# Sheet1.net
KiCad netlist of a schematic drawn in Altium Designer
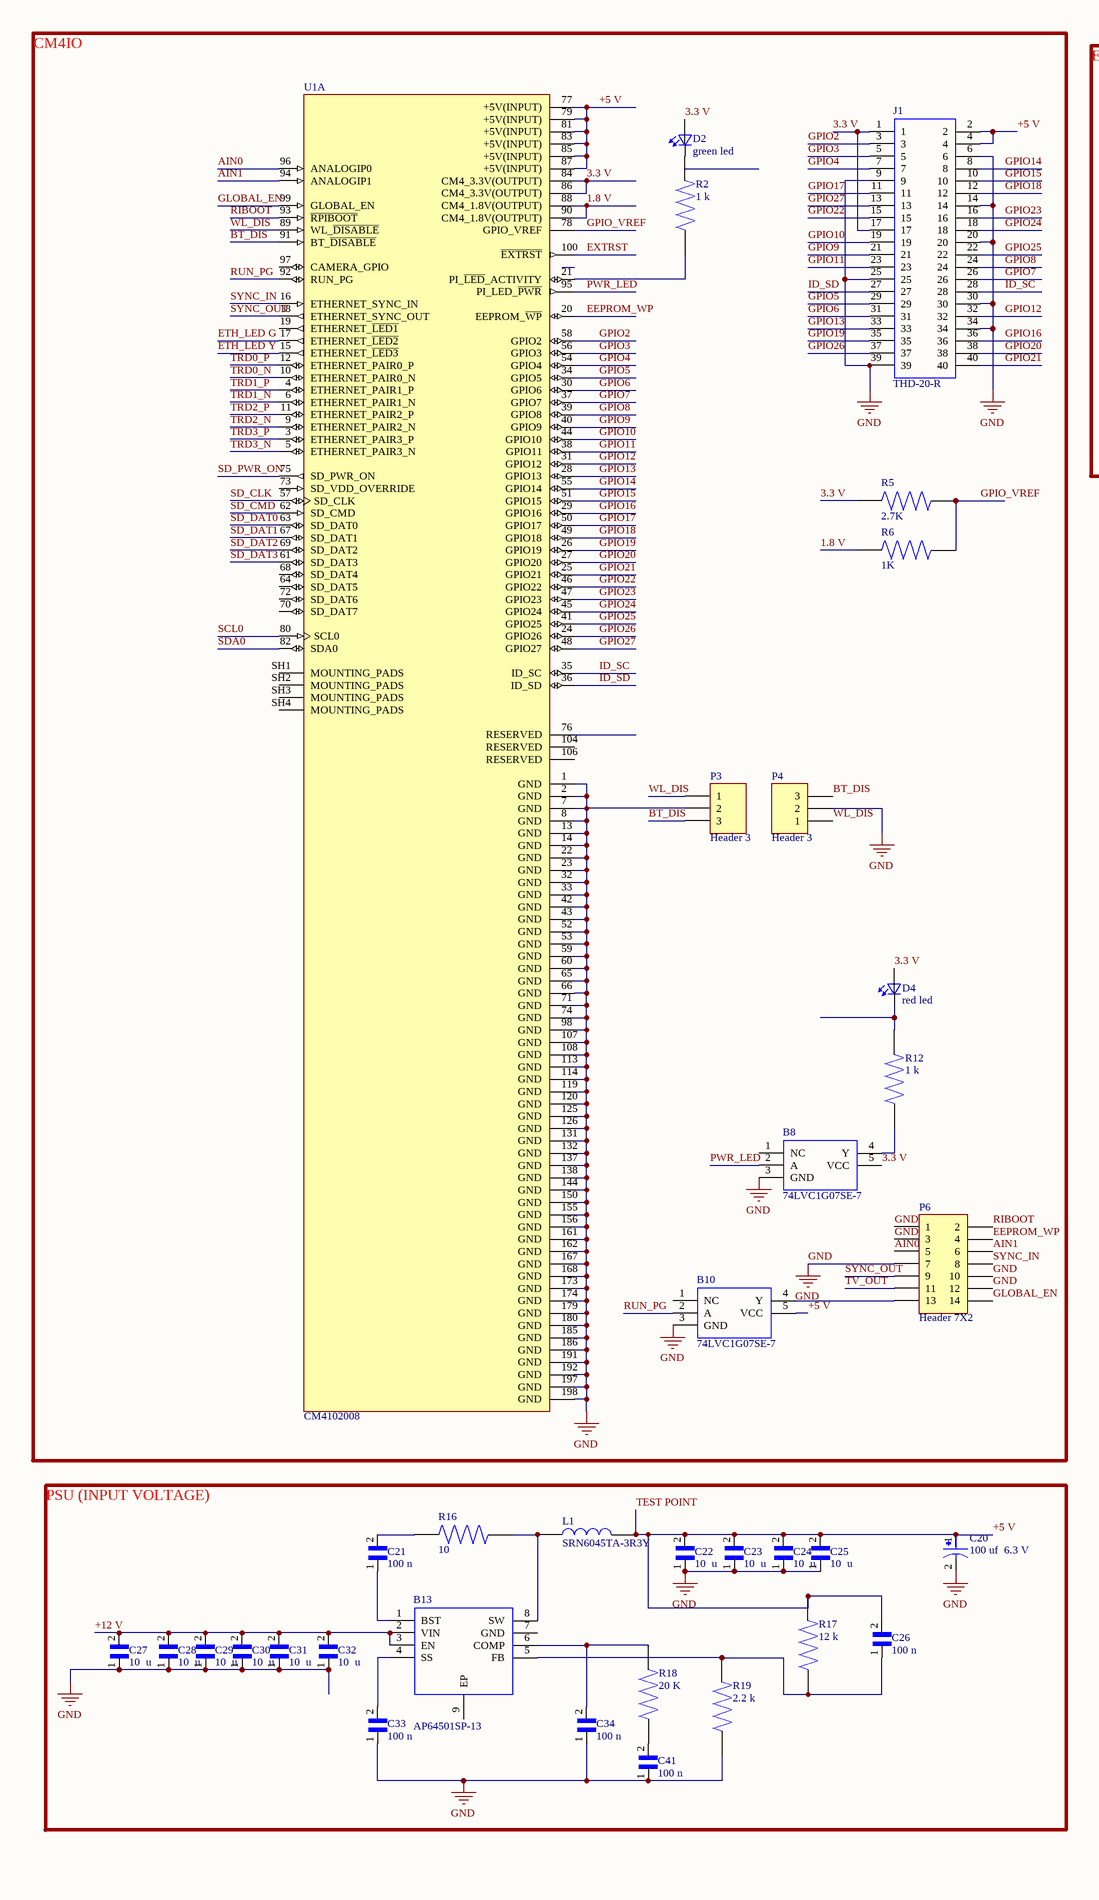
[diagram p0: Sheet1.SchDoc, left]
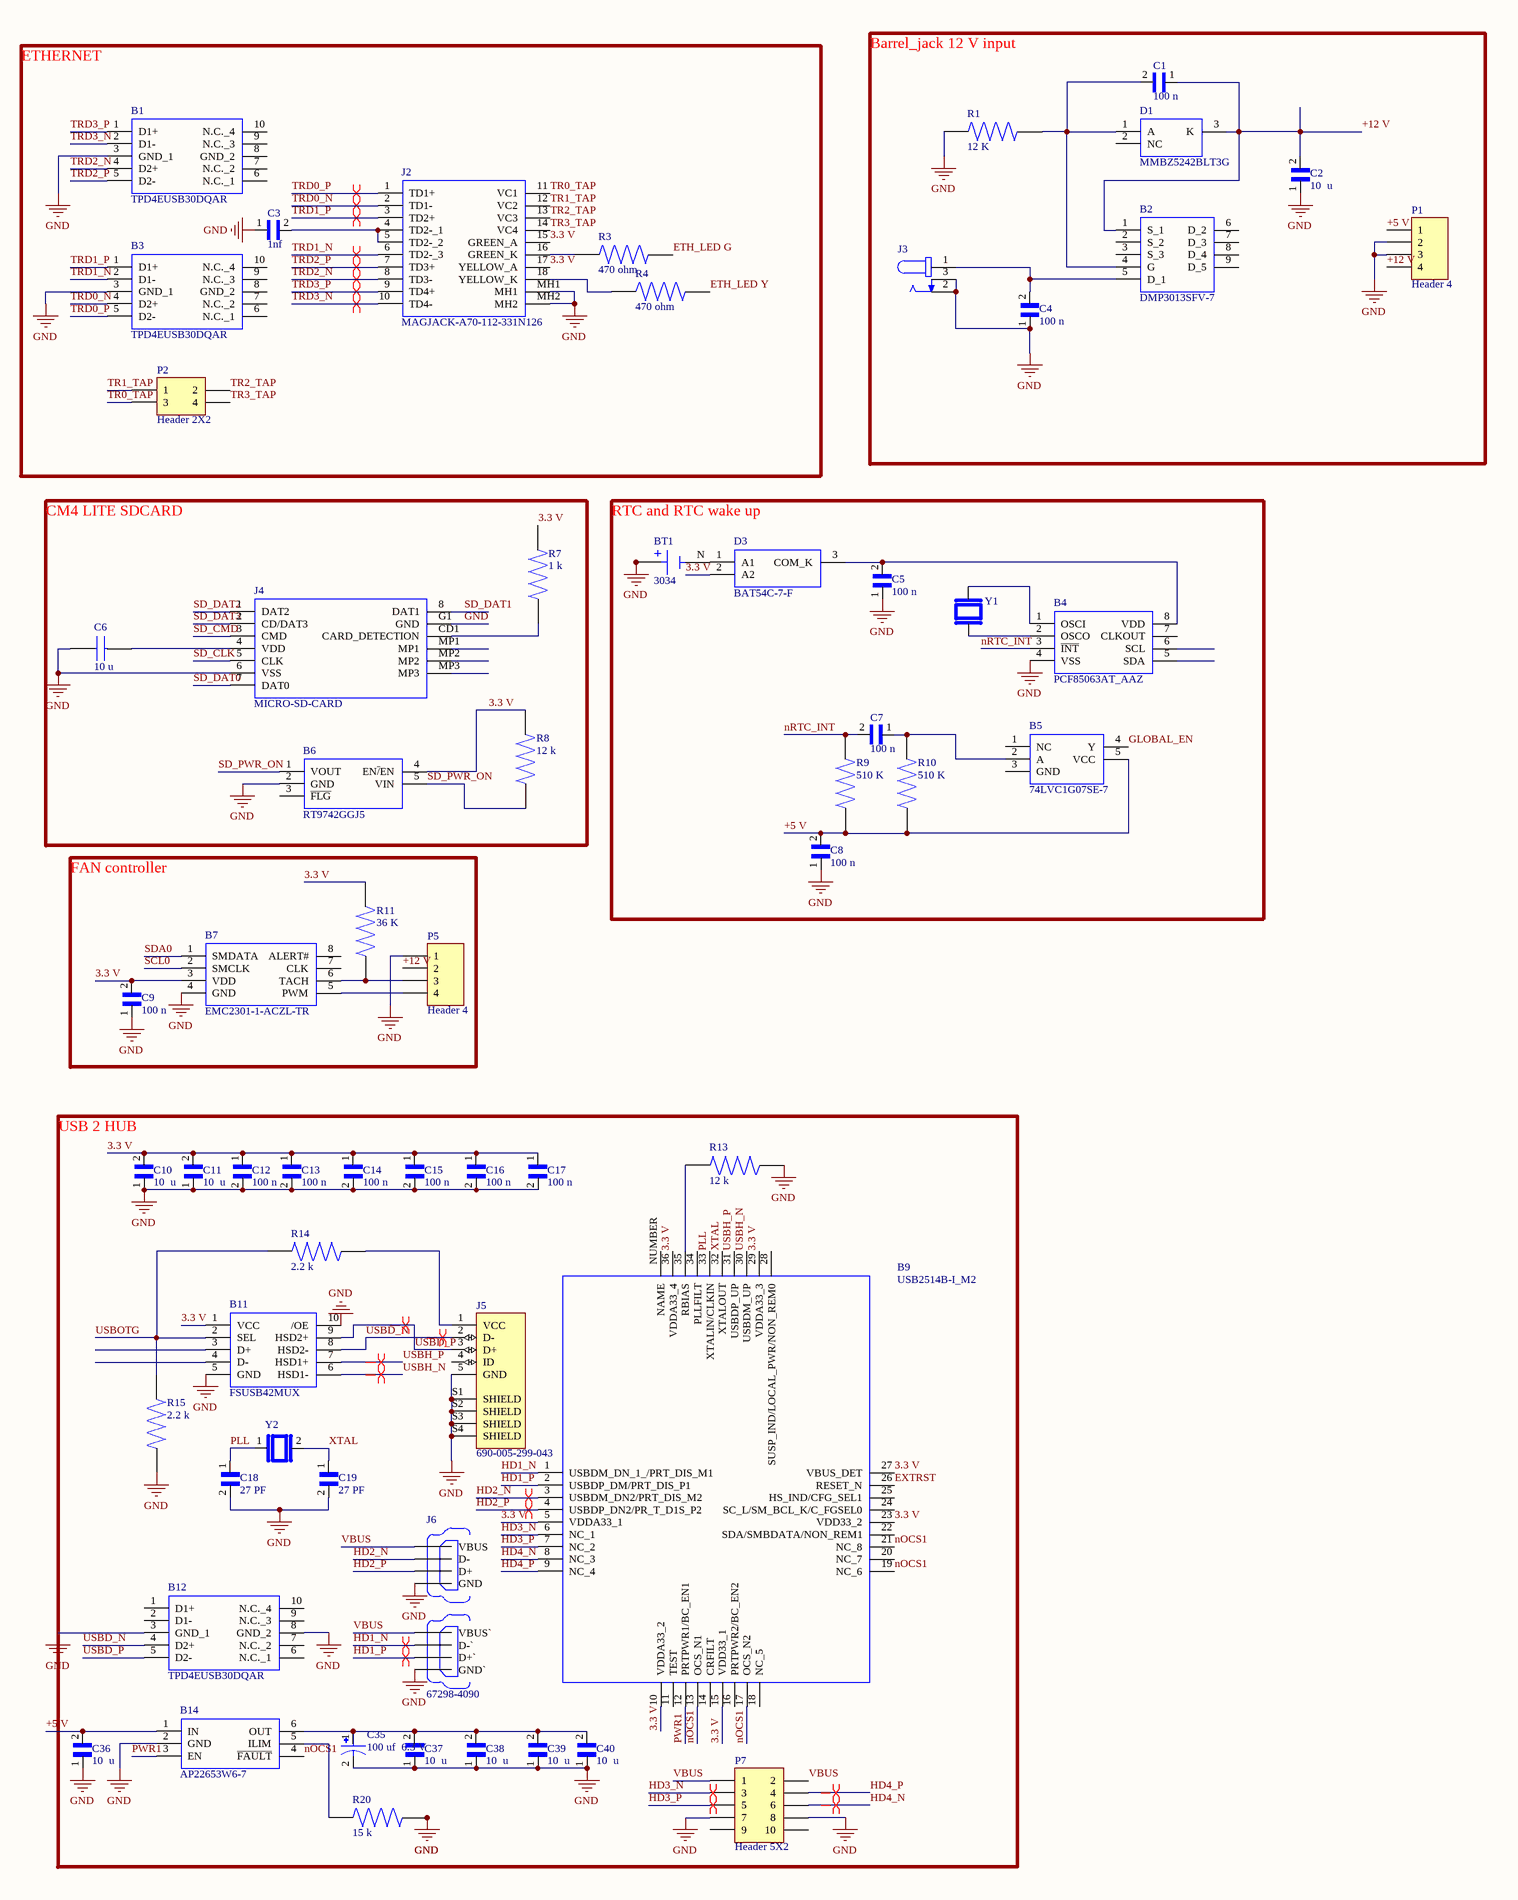
[diagram p1: Sheet1.SchDoc, right]

(export (version "E")
  (design (tool "Eeschema 10.0.6"))
  (components
    (comp (ref "B1")
      (value "TPD4EUSB30DQAR")
      (footprint "DQA_R-PUSON-N10_:DQA(R-PUSON-N10)")
      (description "Texas Instruments TPD4EUSB30DQAR, USB Controller, 6Gbit/s, USB 3.0, 10-Pin SON")
      (fields (field (name "MOUSER PART NUMBER") "595-TPD4EUSB30DQAR"))
      (libsource (lib "Miscellaneous Devices") (part "TPD4EUSB30DQAR"))
    )
    (comp (ref "B2")
      (value "DMP3013SFV-7")
      (footprint "DMP3036SFV7:DMP3036SFV7")
      (description "Trans MOSFET P-CH 30V 12A 8-Pin PowerDI EP T/R")
      (fields (field (name "MOUSER PART NUMBER") "621-DMP3013SFV-7"))
      (libsource (lib "Miscellaneous Devices") (part "DMP3013SFV-7"))
    )
    (comp (ref "B3")
      (value "TPD4EUSB30DQAR")
      (footprint "DQA_R-PUSON-N10_:DQA(R-PUSON-N10)")
      (description "Texas Instruments TPD4EUSB30DQAR, USB Controller, 6Gbit/s, USB 3.0, 10-Pin SON")
      (fields (field (name "MOUSER PART NUMBER") "595-TPD4EUSB30DQAR"))
      (libsource (lib "Miscellaneous Devices") (part "TPD4EUSB30DQAR"))
    )
    (comp (ref "B4")
      (value "PCF85063AT_AAZ")
      (footprint "SOIC127P600X175-8N")
      (description "Real Time Clock Low Power Real time clocks")
      (fields
        (field (name "MANUFACTURER_PART_NUMBER") "PCF85063AT/AAZ")
        (field (name "MOUSER PART NUMBER") "771-PCF85063AT/AAZ")
      )
      (libsource (lib "Miscellaneous Devices") (part "PCF85063AT_AAZ"))
    )
    (comp (ref "B5")
      (value "74LVC1G07SE-7")
      (footprint "SOT65P210X110-5N")
      (description "Buffers & Line Drivers Single Gate Open Out 1.65 to 5.5V 32mA")
      (fields (field (name "MOUSER PART NUMBER") "621-74LVC1G07SE-7"))
      (libsource (lib "Miscellaneous Devices") (part "74LVC1G07SE-7"))
    )
    (comp (ref "B6")
      (value "RT9742GGJ5")
      (footprint "SOT94P280X100-5N")
      (fields (field (name "MOUSER PART NUMBER") "835-RT9742GGJ5"))
      (libsource (lib "Miscellaneous Devices") (part "RT9742GGJ5"))
    )
    (comp (ref "B7")
      (value "EMC2301-1-ACZL-TR")
      (footprint "SOP65P490X110-8N")
      (description "RPM-Based PWM Fan Speed Controller MSOP8")
      (fields (field (name "MOUSER PART NUMBER") "886-EMC2301-1-ACZLTR"))
      (libsource (lib "Miscellaneous Devices") (part "EMC2301-1-ACZL-TR"))
    )
    (comp (ref "B8")
      (value "74LVC1G07SE-7")
      (footprint "SOT65P210X110-5N")
      (description "Buffers & Line Drivers Single Gate Open Out 1.65 to 5.5V 32mA")
      (fields (field (name "MOUSER PART NUMBER") "621-74LVC1G07SE-7"))
      (libsource (lib "Miscellaneous Devices") (part "74LVC1G07SE-7"))
    )
    (comp (ref "B9")
      (value "USB2514B-I_M2")
      (footprint "QFN50P600X600X100-37N-D")
      (description "Microchip USB2514B-I/M2, USB Controller, USB 2.0, 3.3 V, 36-Pin SQFN")
      (fields
        (field (name "MANUFACTURER_PART_NUMBER") "USB2514B-I/M2")
        (field (name "MOUSER PART NUMBER") "579-USB2514B-I/M2")
      )
      (libsource (lib "Miscellaneous Devices") (part "USB2514B-I_M2"))
    )
    (comp (ref "B10")
      (value "74LVC1G07SE-7")
      (footprint "SOT65P210X110-5N")
      (description "Buffers & Line Drivers Single Gate Open Out 1.65 to 5.5V 32mA")
      (fields (field (name "MOUSER PART NUMBER") "621-74LVC1G07SE-7"))
      (libsource (lib "Miscellaneous Devices") (part "74LVC1G07SE-7"))
    )
    (comp (ref "B11")
      (value "FSUSB42MUX")
      (footprint "SOP50P490X110-10N")
      (fields (field (name "MOUSER PART NUMBER") "512-FSUSB42MUX"))
      (libsource (lib "Miscellaneous Devices") (part "FSUSB42MUX"))
    )
    (comp (ref "B12")
      (value "TPD4EUSB30DQAR")
      (footprint "DQA_R-PUSON-N10_:DQA(R-PUSON-N10)")
      (description "Texas Instruments TPD4EUSB30DQAR, USB Controller, 6Gbit/s, USB 3.0, 10-Pin SON")
      (fields (field (name "MOUSER PART NUMBER") "595-TPD4EUSB30DQAR"))
      (libsource (lib "Miscellaneous Devices") (part "TPD4EUSB30DQAR"))
    )
    (comp (ref "B13")
      (value "AP64501SP-13")
      (footprint "SOIC127P600X163-9N")
      (description "Conv DC-DC 3.8V to 40V Synchronous Step Down Single-Out 0.8V to 39V 5A 8-Pin SO EP T/R")
      (fields (field (name "MOUSER PART NUMBER") "621-AP64501SP-13"))
      (libsource (lib "Miscellaneous Devices") (part "AP64501SP-13"))
    )
    (comp (ref "B14")
      (value "AP22653W6-7")
      (footprint "SOT95P280X145-6N")
      (description "Power Switch ICs - Power Distribution 1-Ch Precision Curr-Limit Load SW")
      (fields (field (name "MOUSER PART NUMBER") "621-AP22653W6-7"))
      (libsource (lib "Miscellaneous Devices") (part "AP22653W6-7"))
    )
    (comp (ref "BT1")
      (value "3034")
      (footprint "BAT_3034:BAT_3034")
      (description "SMT Holder for 20mm Cell-Tin Nickel Plate")
      (fields (field (name "MF") "Keystone Electronics Corp."))
      (libsource (lib "Miscellaneous Devices") (part "3034"))
    )
    (comp (ref "C1")
      (value "100 n")
      (footprint "CAPC1005X55N:CAPC1005X55N")
      (description "C Series 0402 0.1 uF 16 V Â±20 % Tolerance X7R SMT Multilayer Ceramic Capacitor")
      (fields (field (name "MP") "C1005X7R1C104M050BC") (field (name "MF") "TDK"))
      (libsource (lib "") (part "C1005X7R1C104M050BC_3"))
    )
    (comp (ref "C2")
      (value "10  u")
      (footprint "CAPC1005X55N:CAPC1005X55N")
      (description "C Series 0805 10 uF 16 V Â±10 % Tolerance X6S SMT Multilayer Ceramic Capacitor")
      (fields (field (name "MP") "C2012X6S1C106K125AC") (field (name "MF") "TDK"))
      (libsource (lib "Miscellaneous Devices") (part "C2012X6S1C106K125AC"))
    )
    (comp (ref "C3")
      (value "1nf")
      (footprint "CAPC1005X55N:CAPC1005X55N")
      (description "C Series 0402 0.1 uF 16 V Â±20 % Tolerance X7R SMT Multilayer Ceramic Capacitor")
      (fields (field (name "MP") "C1005X7R1C104M050BC") (field (name "MF") "TDK"))
      (libsource (lib "") (part "C1005X7R1C104M050BC_2"))
    )
    (comp (ref "C4")
      (value "100 n")
      (footprint "CAPC1005X55N:CAPC1005X55N")
      (description "C Series 0402 0.1 uF 16 V Â±20 % Tolerance X7R SMT Multilayer Ceramic Capacitor")
      (fields (field (name "MP") "C1005X7R1C104M050BC") (field (name "MF") "TDK"))
      (libsource (lib "") (part "C1005X7R1C104M050BC_1"))
    )
    (comp (ref "C5")
      (value "100 n")
      (footprint "CAPC1005X55N:CAPC1005X55N")
      (description "C Series 0402 0.1 uF 16 V Â±20 % Tolerance X7R SMT Multilayer Ceramic Capacitor")
      (fields (field (name "MP") "C1005X7R1C104M050BC") (field (name "MF") "TDK"))
      (libsource (lib "") (part "C1005X7R1C104M050BC_1"))
    )
    (comp (ref "C6")
      (value "10 u")
      (footprint "CAPC2012X145N:CAPC2012X145N")
      (description "Multilayer Ceramic Capacitors MLCC - SMD/SMT 0805 10uF 35volts *Derate Voltage/Temp")
      (fields
        (field (name "MOUSER PART NUMBER") "81-GRM21BC8YA106ME1L")
        (field (name "MANUFACTURER_PART_NUMBER") "GRM21BC8YA106ME11L")
      )
      (libsource (lib "Miscellaneous Devices") (part "GRM21BC8YA106ME11L"))
    )
    (comp (ref "C7")
      (value "100 n")
      (footprint "CAPC1005X55N:CAPC1005X55N")
      (description "C Series 0402 0.1 uF 16 V Â±20 % Tolerance X7R SMT Multilayer Ceramic Capacitor")
      (fields (field (name "MP") "C1005X7R1C104M050BC") (field (name "MF") "TDK"))
      (libsource (lib "") (part "C1005X7R1C104M050BC_3"))
    )
    (comp (ref "C8")
      (value "100 n")
      (footprint "CAPC1005X55N:CAPC1005X55N")
      (description "C Series 0402 0.1 uF 16 V Â±20 % Tolerance X7R SMT Multilayer Ceramic Capacitor")
      (fields (field (name "MP") "C1005X7R1C104M050BC") (field (name "MF") "TDK"))
      (libsource (lib "") (part "C1005X7R1C104M050BC_1"))
    )
    (comp (ref "C9")
      (value "100 n")
      (footprint "CAPC1005X55N:CAPC1005X55N")
      (description "C Series 0402 0.1 uF 16 V Â±20 % Tolerance X7R SMT Multilayer Ceramic Capacitor")
      (fields (field (name "MP") "C1005X7R1C104M050BC") (field (name "MF") "TDK"))
      (libsource (lib "") (part "C1005X7R1C104M050BC_1"))
    )
    (comp (ref "C10")
      (value "10  u")
      (footprint "CAPC1005X55N:CAPC1005X55N")
      (description "C Series 0805 10 uF 16 V Â±10 % Tolerance X6S SMT Multilayer Ceramic Capacitor")
      (fields (field (name "MP") "C2012X6S1C106K125AC") (field (name "MF") "TDK"))
      (libsource (lib "Miscellaneous Devices") (part "C2012X6S1C106K125AC"))
    )
    (comp (ref "C11")
      (value "10  u")
      (footprint "CAPC1005X55N:CAPC1005X55N")
      (description "C Series 0805 10 uF 16 V Â±10 % Tolerance X6S SMT Multilayer Ceramic Capacitor")
      (fields (field (name "MP") "C2012X6S1C106K125AC") (field (name "MF") "TDK"))
      (libsource (lib "Miscellaneous Devices") (part "C2012X6S1C106K125AC"))
    )
    (comp (ref "C12")
      (value "100 n")
      (footprint "CAPC1005X55N:CAPC1005X55N")
      (description "C Series 0402 0.1 uF 16 V Â±20 % Tolerance X7R SMT Multilayer Ceramic Capacitor")
      (fields (field (name "MP") "C1005X7R1C104M050BC") (field (name "MF") "TDK"))
      (libsource (lib "Miscellaneous Devices") (part "C1005X7R1C104M050BC"))
    )
    (comp (ref "C13")
      (value "100 n")
      (footprint "CAPC1005X55N:CAPC1005X55N")
      (description "C Series 0402 0.1 uF 16 V Â±20 % Tolerance X7R SMT Multilayer Ceramic Capacitor")
      (fields (field (name "MP") "C1005X7R1C104M050BC") (field (name "MF") "TDK"))
      (libsource (lib "Miscellaneous Devices") (part "C1005X7R1C104M050BC"))
    )
    (comp (ref "C14")
      (value "100 n")
      (footprint "CAPC1005X55N:CAPC1005X55N")
      (description "C Series 0402 0.1 uF 16 V Â±20 % Tolerance X7R SMT Multilayer Ceramic Capacitor")
      (fields (field (name "MP") "C1005X7R1C104M050BC") (field (name "MF") "TDK"))
      (libsource (lib "Miscellaneous Devices") (part "C1005X7R1C104M050BC"))
    )
    (comp (ref "C15")
      (value "100 n")
      (footprint "CAPC1005X55N:CAPC1005X55N")
      (description "C Series 0402 0.1 uF 16 V Â±20 % Tolerance X7R SMT Multilayer Ceramic Capacitor")
      (fields (field (name "MP") "C1005X7R1C104M050BC") (field (name "MF") "TDK"))
      (libsource (lib "Miscellaneous Devices") (part "C1005X7R1C104M050BC"))
    )
    (comp (ref "C16")
      (value "100 n")
      (footprint "CAPC1005X55N:CAPC1005X55N")
      (description "C Series 0402 0.1 uF 16 V Â±20 % Tolerance X7R SMT Multilayer Ceramic Capacitor")
      (fields (field (name "MP") "C1005X7R1C104M050BC") (field (name "MF") "TDK"))
      (libsource (lib "Miscellaneous Devices") (part "C1005X7R1C104M050BC"))
    )
    (comp (ref "C17")
      (value "100 n")
      (footprint "CAPC1005X55N:CAPC1005X55N")
      (description "C Series 0402 0.1 uF 16 V Â±20 % Tolerance X7R SMT Multilayer Ceramic Capacitor")
      (fields (field (name "MP") "C1005X7R1C104M050BC") (field (name "MF") "TDK"))
      (libsource (lib "Miscellaneous Devices") (part "C1005X7R1C104M050BC"))
    )
    (comp (ref "C18")
      (value "27 PF")
      (footprint "CAPC1005X55N:CAPC1005X55N")
      (description "C Series 0402 0.1 uF 16 V Â±20 % Tolerance X7R SMT Multilayer Ceramic Capacitor")
      (fields (field (name "MP") "C1005X7R1C104M050BC") (field (name "MF") "TDK"))
      (libsource (lib "Miscellaneous Devices") (part "C1005X7R1C104M050BC"))
    )
    (comp (ref "C19")
      (value "27 PF")
      (footprint "CAPC1005X55N:CAPC1005X55N")
      (description "C Series 0402 0.1 uF 16 V Â±20 % Tolerance X7R SMT Multilayer Ceramic Capacitor")
      (fields (field (name "MP") "C1005X7R1C104M050BC") (field (name "MF") "TDK"))
      (libsource (lib "Miscellaneous Devices") (part "C1005X7R1C104M050BC"))
    )
    (comp (ref "C20")
      (value "100 uf  6.3 V")
      (footprint "CAPMP3528X210N:CAPMP3528X210N")
      (description "100 ÂµF Molded Tantalum Polymer Capacitor 6.3 V 1411 (3528 Metric) 25mOhm @ 100kHz")
      (fields (field (name "MF") "KEMET") (field (name "MP") "T543B107K006AHW025"))
      (libsource (lib "Miscellaneous Devices") (part "T543B107K006AHW025"))
    )
    (comp (ref "C21")
      (value "100 n")
      (footprint "CAPC1005X55N:CAPC1005X55N")
      (description "C Series 0402 0.1 uF 16 V Â±20 % Tolerance X7R SMT Multilayer Ceramic Capacitor")
      (fields (field (name "MP") "C1005X7R1C104M050BC") (field (name "MF") "TDK"))
      (libsource (lib "") (part "C1005X7R1C104M050BC_1"))
    )
    (comp (ref "C22")
      (value "10  u")
      (footprint "CAPC1005X55N:CAPC1005X55N")
      (description "C Series 0805 10 uF 16 V Â±10 % Tolerance X6S SMT Multilayer Ceramic Capacitor")
      (fields (field (name "MP") "C2012X6S1C106K125AC") (field (name "MF") "TDK"))
      (libsource (lib "Miscellaneous Devices") (part "C2012X6S1C106K125AC"))
    )
    (comp (ref "C23")
      (value "10  u")
      (footprint "CAPC1005X55N:CAPC1005X55N")
      (description "C Series 0805 10 uF 16 V Â±10 % Tolerance X6S SMT Multilayer Ceramic Capacitor")
      (fields (field (name "MP") "C2012X6S1C106K125AC") (field (name "MF") "TDK"))
      (libsource (lib "Miscellaneous Devices") (part "C2012X6S1C106K125AC"))
    )
    (comp (ref "C24")
      (value "10  u")
      (footprint "CAPC1005X55N:CAPC1005X55N")
      (description "C Series 0805 10 uF 16 V Â±10 % Tolerance X6S SMT Multilayer Ceramic Capacitor")
      (fields (field (name "MP") "C2012X6S1C106K125AC") (field (name "MF") "TDK"))
      (libsource (lib "Miscellaneous Devices") (part "C2012X6S1C106K125AC"))
    )
    (comp (ref "C25")
      (value "10  u")
      (footprint "CAPC1005X55N:CAPC1005X55N")
      (description "C Series 0805 10 uF 16 V Â±10 % Tolerance X6S SMT Multilayer Ceramic Capacitor")
      (fields (field (name "MP") "C2012X6S1C106K125AC") (field (name "MF") "TDK"))
      (libsource (lib "Miscellaneous Devices") (part "C2012X6S1C106K125AC"))
    )
    (comp (ref "C26")
      (value "100 n")
      (footprint "CAPC1005X55N:CAPC1005X55N")
      (description "C Series 0402 0.1 uF 16 V Â±20 % Tolerance X7R SMT Multilayer Ceramic Capacitor")
      (fields (field (name "MP") "C1005X7R1C104M050BC") (field (name "MF") "TDK"))
      (libsource (lib "") (part "C1005X7R1C104M050BC_1"))
    )
    (comp (ref "C27")
      (value "10  u")
      (footprint "CAPC1005X55N:CAPC1005X55N")
      (description "C Series 0805 10 uF 16 V Â±10 % Tolerance X6S SMT Multilayer Ceramic Capacitor")
      (fields (field (name "MP") "C2012X6S1C106K125AC") (field (name "MF") "TDK"))
      (libsource (lib "Miscellaneous Devices") (part "C2012X6S1C106K125AC"))
    )
    (comp (ref "C28")
      (value "10  u")
      (footprint "CAPC1005X55N:CAPC1005X55N")
      (description "C Series 0805 10 uF 16 V Â±10 % Tolerance X6S SMT Multilayer Ceramic Capacitor")
      (fields (field (name "MP") "C2012X6S1C106K125AC") (field (name "MF") "TDK"))
      (libsource (lib "Miscellaneous Devices") (part "C2012X6S1C106K125AC"))
    )
    (comp (ref "C29")
      (value "10  u")
      (footprint "CAPC1005X55N:CAPC1005X55N")
      (description "C Series 0805 10 uF 16 V Â±10 % Tolerance X6S SMT Multilayer Ceramic Capacitor")
      (fields (field (name "MP") "C2012X6S1C106K125AC") (field (name "MF") "TDK"))
      (libsource (lib "Miscellaneous Devices") (part "C2012X6S1C106K125AC"))
    )
    (comp (ref "C30")
      (value "10  u")
      (footprint "CAPC1005X55N:CAPC1005X55N")
      (description "C Series 0805 10 uF 16 V Â±10 % Tolerance X6S SMT Multilayer Ceramic Capacitor")
      (fields (field (name "MP") "C2012X6S1C106K125AC") (field (name "MF") "TDK"))
      (libsource (lib "Miscellaneous Devices") (part "C2012X6S1C106K125AC"))
    )
    (comp (ref "C31")
      (value "10  u")
      (footprint "CAPC1005X55N:CAPC1005X55N")
      (description "C Series 0805 10 uF 16 V Â±10 % Tolerance X6S SMT Multilayer Ceramic Capacitor")
      (fields (field (name "MP") "C2012X6S1C106K125AC") (field (name "MF") "TDK"))
      (libsource (lib "Miscellaneous Devices") (part "C2012X6S1C106K125AC"))
    )
    (comp (ref "C32")
      (value "10  u")
      (footprint "CAPC1005X55N:CAPC1005X55N")
      (description "C Series 0805 10 uF 16 V Â±10 % Tolerance X6S SMT Multilayer Ceramic Capacitor")
      (fields (field (name "MP") "C2012X6S1C106K125AC") (field (name "MF") "TDK"))
      (libsource (lib "Miscellaneous Devices") (part "C2012X6S1C106K125AC"))
    )
    (comp (ref "C33")
      (value "100 n")
      (footprint "CAPC1005X55N:CAPC1005X55N")
      (description "C Series 0402 0.1 uF 16 V Â±20 % Tolerance X7R SMT Multilayer Ceramic Capacitor")
      (fields (field (name "MP") "C1005X7R1C104M050BC") (field (name "MF") "TDK"))
      (libsource (lib "") (part "C1005X7R1C104M050BC_1"))
    )
    (comp (ref "C34")
      (value "100 n")
      (footprint "CAPC1005X55N:CAPC1005X55N")
      (description "C Series 0402 0.1 uF 16 V Â±20 % Tolerance X7R SMT Multilayer Ceramic Capacitor")
      (fields (field (name "MP") "C1005X7R1C104M050BC") (field (name "MF") "TDK"))
      (libsource (lib "") (part "C1005X7R1C104M050BC_1"))
    )
    (comp (ref "C35")
      (value "100 uf  6.3 V")
      (footprint "CAPMP3528X210N:CAPMP3528X210N")
      (description "100 ÂµF Molded Tantalum Polymer Capacitor 6.3 V 1411 (3528 Metric) 25mOhm @ 100kHz")
      (fields (field (name "MF") "KEMET") (field (name "MP") "T543B107K006AHW025"))
      (libsource (lib "Miscellaneous Devices") (part "T543B107K006AHW025"))
    )
    (comp (ref "C36")
      (value "10  u")
      (footprint "CAPC1005X55N:CAPC1005X55N")
      (description "C Series 0805 10 uF 16 V Â±10 % Tolerance X6S SMT Multilayer Ceramic Capacitor")
      (fields (field (name "MP") "C2012X6S1C106K125AC") (field (name "MF") "TDK"))
      (libsource (lib "Miscellaneous Devices") (part "C2012X6S1C106K125AC"))
    )
    (comp (ref "C37")
      (value "10  u")
      (footprint "CAPC1005X55N:CAPC1005X55N")
      (description "C Series 0805 10 uF 16 V Â±10 % Tolerance X6S SMT Multilayer Ceramic Capacitor")
      (fields (field (name "MP") "C2012X6S1C106K125AC") (field (name "MF") "TDK"))
      (libsource (lib "Miscellaneous Devices") (part "C2012X6S1C106K125AC"))
    )
    (comp (ref "C38")
      (value "10  u")
      (footprint "CAPC1005X55N:CAPC1005X55N")
      (description "C Series 0805 10 uF 16 V Â±10 % Tolerance X6S SMT Multilayer Ceramic Capacitor")
      (fields (field (name "MP") "C2012X6S1C106K125AC") (field (name "MF") "TDK"))
      (libsource (lib "Miscellaneous Devices") (part "C2012X6S1C106K125AC"))
    )
    (comp (ref "C39")
      (value "10  u")
      (footprint "CAPC1005X55N:CAPC1005X55N")
      (description "C Series 0805 10 uF 16 V Â±10 % Tolerance X6S SMT Multilayer Ceramic Capacitor")
      (fields (field (name "MP") "C2012X6S1C106K125AC") (field (name "MF") "TDK"))
      (libsource (lib "Miscellaneous Devices") (part "C2012X6S1C106K125AC"))
    )
    (comp (ref "C40")
      (value "10  u")
      (footprint "CAPC1005X55N:CAPC1005X55N")
      (description "C Series 0805 10 uF 16 V Â±10 % Tolerance X6S SMT Multilayer Ceramic Capacitor")
      (fields (field (name "MP") "C2012X6S1C106K125AC") (field (name "MF") "TDK"))
      (libsource (lib "Miscellaneous Devices") (part "C2012X6S1C106K125AC"))
    )
    (comp (ref "C41")
      (value "100 n")
      (footprint "CAPC1005X55N:CAPC1005X55N")
      (description "C Series 0402 0.1 uF 16 V Â±20 % Tolerance X7R SMT Multilayer Ceramic Capacitor")
      (fields (field (name "MP") "C1005X7R1C104M050BC") (field (name "MF") "TDK"))
      (libsource (lib "") (part "C1005X7R1C104M050BC_1"))
    )
    (comp (ref "D1")
      (value "MMBZ5242BLT3G")
      (footprint "SOT96P237X111-3N")
      (fields (field (name "MOUSER PART NUMBER") "863-MMBZ5242BLT3G"))
      (libsource (lib "Miscellaneous Devices") (part "MMBZ5242BLT3G"))
    )
    (comp (ref "D2")
      (value "green led")
      (footprint "SnapEDApcb:0603")
      (description "Green 571nm LED Indication - Discrete 2V 0603 _1608 Metric_")
      (fields (field (name "MP") "LTST-S270KGKT") (field (name "MF") "Lite-On Inc."))
      (libsource (lib "Miscellaneous Devices") (part "LTST-S270KGKT"))
    )
    (comp (ref "D3")
      (value "BAT54C-7-F")
      (footprint "SOT96P240X115-3N")
      (description "DiodesZetex   ,  30V, 3 SOT-23,  +150 C")
      (fields (field (name "MOUSER PART NUMBER") "621-BAT54C-F"))
      (libsource (lib "Miscellaneous Devices") (part "BAT54C-7-F"))
    )
    (comp (ref "D4")
      (value "red led")
      (footprint "SnapEDApcb:0603")
      (description "http://octopart.com/ltst-c190tbkt-lite-on-550003")
      (fields (field (name "MF") "{'manufacturer': u'Lite-On Inc.'}") (field (name "MP") "LTST-S270KRKT"))
      (libsource (lib "Miscellaneous Devices") (part "LTST-S270KRKT"))
    )
    (comp (ref "J1")
      (value "THD-20-R")
      (footprint "HDRV40W66P254_2X20_5080X500X890P")
      (libsource (lib "Miscellaneous Devices") (part "THD-20-R"))
    )
    (comp (ref "J2")
      (value "MAGJACK-A70-112-331N126")
      (footprint "EDAC_A70-112-331N126")
      (description "1 Port RJ45 Magjack Connector Through Hole 10/100 Base-T, AutoMDIX")
      (libsource (lib "MAGJACK-A70-112-331N126") (part "MAGJACK-A70-112-331N126"))
    )
    (comp (ref "J3")
      (value "DCJ200-10-A-XX-K_REVA")
      (footprint "GCT_DCJ200-10-A-XX-K_REVA")
      (description "Power Barrel Connector Jack 2.05mm ID (0.081), 5.50mm OD (0.217) Through Hole, Right Angle")
      (fields (field (name "MF") "Global Connector Technology") (field (name "MP") "DCJ200-10-A-K1-K"))
      (libsource (lib "Miscellaneous Devices") (part "DCJ200-10-A-XX-K_REVA"))
    )
    (comp (ref "J4")
      (value "MICRO-SD-CARD")
      (footprint "MICROSDCARD")
      (description "Memory Card Connectors MICRO SD CARD CONNECTOR WITH PUSH PUSH EJECT ACTION")
      (libsource (lib "Miscellaneous Devices") (part "MICRO-SD-CARD"))
    )
    (comp (ref "J5")
      (value "690-005-299-043")
      (footprint "EDAC_690-005-299-043:EDAC_690-005-299-043")
      (description "USB - mini B USB 2.0 Receptacle Connector 5 Position Surface Mount, Right Angle")
      (fields (field (name "MF") "EDAC Inc."))
      (libsource (lib "Miscellaneous Devices") (part "690-005-299-043"))
    )
    (comp (ref "J6")
      (value "67298-4090")
      (footprint "MOLEX_67298-4090")
      (description "USB-A (USB TYPE-A), Stacked - Receptacle Connector 8 Position Through Hole, Right Angle")
      (fields (field (name "MF") "Molex"))
      (libsource (lib "Miscellaneous Devices") (part "67298-4090"))
    )
    (comp (ref "L1")
      (value "SRN6045TA-3R3Y")
      (footprint "SRN6045TA330M")
      (description "BOURNS - SRN6045TA-3R3Y - INDUCTOR, AEC-Q200, 3.3UH, 5A, 30% Semi-shielded Power Inductors")
      (fields (field (name "MOUSER PART NUMBER") "652-SRN6045TA-3R3Y"))
      (libsource (lib "Miscellaneous Devices") (part "SRN6045TA-3R3Y"))
    )
    (comp (ref "P1")
      (value "Header 4")
      (footprint "HDR1X4")
      (description "Header, 4-Pin")
      (fields (field (name "PUBLISHER") "Altium Limited"))
      (libsource (lib "Miscellaneous Devices") (part "Header 4"))
    )
    (comp (ref "P2")
      (value "Header 2X2")
      (footprint "HDR2X2")
      (description "Header, 2-Pin, Dual row")
      (fields (field (name "PUBLISHER") "Altium Limited"))
      (libsource (lib "Miscellaneous Devices") (part "Header 2X2"))
    )
    (comp (ref "P3")
      (value "Header 3")
      (footprint "HDR1X3")
      (description "Header, 3-Pin")
      (fields (field (name "PUBLISHER") "Altium Limited"))
      (libsource (lib "Miscellaneous Devices") (part "Header 3"))
    )
    (comp (ref "P4")
      (value "Header 3")
      (footprint "HDR1X3")
      (description "Header, 3-Pin")
      (fields (field (name "PUBLISHER") "Altium Limited"))
      (libsource (lib "") (part "Header 3_1"))
    )
    (comp (ref "P5")
      (value "Header 4")
      (footprint "HDR1X4")
      (description "Header, 4-Pin")
      (fields (field (name "PUBLISHER") "Altium Limited"))
      (libsource (lib "Miscellaneous Devices") (part "Header 4"))
    )
    (comp (ref "P6")
      (value "Header 7X2")
      (footprint "HDR2X7")
      (description "Header, 7-Pin, Dual row")
      (fields (field (name "PUBLISHER") "Altium Limited"))
      (libsource (lib "Miscellaneous Devices") (part "Header 7X2"))
    )
    (comp (ref "P7")
      (value "Header 5X2")
      (footprint "HDR2X5")
      (description "Header, 5-Pin, Dual row")
      (fields (field (name "PUBLISHER") "Altium Limited"))
      (libsource (lib "Miscellaneous Devices") (part "Header 5X2"))
    )
    (comp (ref "R1")
      (value "12 K")
      (footprint "RESC2012X65N")
      (description "Surface Mount Thin Film Resistor, Cpf Series, 12.1 Kohm, 63 Mw, - 0.1%, 25 V")
      (fields (field (name "MP") "CPF0402B12K1E1"))
      (libsource (lib "Miscellaneous Devices") (part "CPF0402B12K1E1"))
    )
    (comp (ref "R2")
      (value "1 k")
      (footprint "RESC1005X35N")
      (description "CPF 0402 1K1 0.1% 25PPM 1K RL")
      (fields (field (name "MP") "CPF0402B1K1E1"))
      (libsource (lib "Miscellaneous Devices") (part "CPF0402B1K1E1"))
    )
    (comp (ref "R3")
      (value "470 ohm")
      (footprint "RESC2012X65N")
      (description "CPF 0402 470R 0.1% 25PPM 1K RL")
      (fields (field (name "MP") "CPF0402B470RE1"))
      (libsource (lib "Miscellaneous Devices") (part "CPF0402B470RE1"))
    )
    (comp (ref "R4")
      (value "470 ohm")
      (footprint "RESC2012X65N")
      (description "CPF 0402 470R 0.1% 25PPM 1K RL")
      (fields (field (name "MP") "CPF0402B470RE1"))
      (libsource (lib "Miscellaneous Devices") (part "CPF0402B470RE1"))
    )
    (comp (ref "R5")
      (value "2.7K")
      (footprint "RESC2012X65N")
      (description "RES SMD 2.7K OHM 0.1% 1/10W 0805")
      (fields (field (name "MP") "CPF0805B2K7E1"))
      (libsource (lib "Miscellaneous Devices") (part "CPF0805B2K7E1"))
    )
    (comp (ref "R6")
      (value "1K")
      (footprint "RESC2012X65N")
      (description "CPF 0805 20R 0.1% 25PPM 1K RL")
      (fields (field (name "MP") "CPF0805B20RE1"))
      (libsource (lib "Miscellaneous Devices") (part "CPF0805B20RE1"))
    )
    (comp (ref "R7")
      (value "1 k")
      (footprint "RESC1005X35N")
      (description "CPF 0402 1K1 0.1% 25PPM 1K RL")
      (fields (field (name "MP") "CPF0402B1K1E1"))
      (libsource (lib "Miscellaneous Devices") (part "CPF0402B1K1E1"))
    )
    (comp (ref "R8")
      (value "12 k")
      (footprint "RESC2012X65N")
      (description "Surface Mount Thin Film Resistor, Cpf Series, 12.1 Kohm, 63 Mw, - 0.1%, 25 V")
      (fields (field (name "MP") "CPF0402B12K1E1"))
      (libsource (lib "Miscellaneous Devices") (part "CPF0402B12K1E1"))
    )
    (comp (ref "R9")
      (value "510 K")
      (footprint "RESC1005X35N")
      (description "CPF 0402 1K1 0.1% 25PPM 1K RL")
      (fields (field (name "MP") "CPF0402B1K1E1"))
      (libsource (lib "Miscellaneous Devices") (part "CPF0402B1K1E1"))
    )
    (comp (ref "R10")
      (value "510 K")
      (footprint "RESC1005X35N")
      (description "CPF 0402 1K1 0.1% 25PPM 1K RL")
      (fields (field (name "MP") "CPF0402B1K1E1"))
      (libsource (lib "Miscellaneous Devices") (part "CPF0402B1K1E1"))
    )
    (comp (ref "R11")
      (value "36 K")
      (footprint "RESC1005X35N")
      (description "CPF 0402 1K1 0.1% 25PPM 1K RL")
      (fields (field (name "MP") "CPF0402B1K1E1"))
      (libsource (lib "Miscellaneous Devices") (part "CPF0402B1K1E1"))
    )
    (comp (ref "R12")
      (value "1 k")
      (footprint "RESC1005X35N")
      (description "CPF 0402 1K1 0.1% 25PPM 1K RL")
      (fields (field (name "MP") "CPF0402B1K1E1"))
      (libsource (lib "Miscellaneous Devices") (part "CPF0402B1K1E1"))
    )
    (comp (ref "R13")
      (value "12 k")
      (footprint "RESC2012X65N")
      (description "Surface Mount Thin Film Resistor, Cpf Series, 12.1 Kohm, 63 Mw, - 0.1%, 25 V")
      (fields (field (name "MP") "CPF0402B12K1E1"))
      (libsource (lib "Miscellaneous Devices") (part "CPF0402B12K1E1"))
    )
    (comp (ref "R14")
      (value "2.2 k")
      (footprint "RESC2012X65N")
      (description "Surface Mount Thin Film Resistor, Cpf Series, 12.1 Kohm, 63 Mw, - 0.1%, 25 V")
      (fields (field (name "MP") "CPF0402B12K1E1"))
      (libsource (lib "Miscellaneous Devices") (part "CPF0402B12K1E1"))
    )
    (comp (ref "R15")
      (value "2.2 k")
      (footprint "RESC2012X65N")
      (description "Surface Mount Thin Film Resistor, Cpf Series, 12.1 Kohm, 63 Mw, - 0.1%, 25 V")
      (fields (field (name "MP") "CPF0402B12K1E1"))
      (libsource (lib "Miscellaneous Devices") (part "CPF0402B12K1E1"))
    )
    (comp (ref "R16")
      (value "10")
      (footprint "RESC2012X65N")
      (description "CPF 0805 20R 0.1% 25PPM 1K RL")
      (fields (field (name "MP") "CPF0805B20RE1"))
      (libsource (lib "Miscellaneous Devices") (part "CPF0805B20RE1"))
    )
    (comp (ref "R17")
      (value "12 k")
      (footprint "RESC2012X65N")
      (description "Surface Mount Thin Film Resistor, Cpf Series, 12.1 Kohm, 63 Mw, - 0.1%, 25 V")
      (fields (field (name "MP") "CPF0402B12K1E1"))
      (libsource (lib "Miscellaneous Devices") (part "CPF0402B12K1E1"))
    )
    (comp (ref "R18")
      (value "20 K")
      (footprint "RESC2012X65N")
      (description "Surface Mount Thin Film Resistor, Cpf Series, 12.1 Kohm, 63 Mw, - 0.1%, 25 V")
      (fields (field (name "MP") "CPF0402B12K1E1"))
      (libsource (lib "Miscellaneous Devices") (part "CPF0402B12K1E1"))
    )
    (comp (ref "R19")
      (value "2.2 k")
      (footprint "RESC1005X35N")
      (description "CPF 0402 2K1 0.1% 25PPM 1K RL")
      (fields (field (name "MP") "CPF0402B2K1E1"))
      (libsource (lib "Miscellaneous Devices") (part "CPF0402B2K1E1"))
    )
    (comp (ref "R20")
      (value "15 k")
      (footprint "RESC2012X65N")
      (description "Surface Mount Thin Film Resistor, Cpf Series, 12.1 Kohm, 63 Mw, - 0.1%, 25 V")
      (fields (field (name "MP") "CPF0402B12K1E1"))
      (libsource (lib "Miscellaneous Devices") (part "CPF0402B12K1E1"))
    )
    (comp (ref "U1")
      (value "CM4102008")
      (footprint "MODULE_CM4102008")
      (description "Raspberry Pi Compute Module 4 with WiFi 2GB RAM 8GB Flash ¦ Raspberry Pi CM4102008")
      (fields (field (name "MF") "Raspberry Pi"))
      (libsource (lib "Miscellaneous Devices") (part "CM4102008"))
    )
    (comp (ref "Y1")
      (value "CM7V-T1A-32.768KHZ-12.5PF-10PPM-TB-QC")
      (footprint "XTAL_CM7V-T1A-32.768KHZ-12.5PF-10PPM-TB-QC")
      (description "Tuning Fork Crystal 32.768kHz in SMD 1.5 x 3.2 mm package")
      (fields (field (name "MF") "Micro Crystal"))
      (libsource (lib "Miscellaneous Devices") (part "CM7V-T1A-32.768KHZ-12.5PF-10PPM-TB-QC"))
    )
    (comp (ref "Y2")
      (value "FOXSDLF/240F-20")
      (footprint "XTAL_FOXSDLF/240F-20")
      (description "24 MHz Â±30 ppm Cristal 20 pF 30 ohmios HC-49/US")
      (fields (field (name "MF") "Fox Electronics"))
      (libsource (lib "Miscellaneous Devices") (part "FOXSDLF/240F-20"))
    )
  )
  (nets
    (net (code "1") (name "/+5 V") (class "Default")
      (node (ref "B10") (pin "5") (pinfunction "VCC_5") (pintype "passive"))
      (node (ref "B14") (pin "1") (pinfunction "IN_1") (pintype "passive"))
      (node (ref "B5") (pin "5") (pinfunction "VCC_5") (pintype "passive"))
      (node (ref "C20") (pin "1") (pinfunction "1_1") (pintype "passive"))
      (node (ref "C22") (pin "2") (pinfunction "2_2") (pintype "passive"))
      (node (ref "C23") (pin "2") (pinfunction "2_2") (pintype "passive"))
      (node (ref "C24") (pin "2") (pinfunction "2_2") (pintype "passive"))
      (node (ref "C25") (pin "2") (pinfunction "2_2") (pintype "passive"))
      (node (ref "C26") (pin "2") (pinfunction "2_2") (pintype "passive"))
      (node (ref "C36") (pin "2") (pinfunction "2_2") (pintype "passive"))
      (node (ref "C8") (pin "2") (pinfunction "2_2") (pintype "passive"))
      (node (ref "J1") (pin "2") (pinfunction "2_2") (pintype "passive"))
      (node (ref "J1") (pin "4") (pinfunction "4_4") (pintype "passive"))
      (node (ref "L1") (pin "2") (pinfunction "2_2") (pintype "passive"))
      (node (ref "P1") (pin "1") (pinfunction "1_1") (pintype "passive"))
      (node (ref "R10") (pin "1") (pinfunction "1_1") (pintype "passive"))
      (node (ref "R17") (pin "2") (pinfunction "2_2") (pintype "passive"))
      (node (ref "R9") (pin "1") (pinfunction "1_1") (pintype "passive"))
      (node (ref "U1") (pin "77") (pinfunction "+5V(INPUT)_77") (pintype "power_in"))
      (node (ref "U1") (pin "79") (pinfunction "+5V(INPUT)_79") (pintype "power_in"))
      (node (ref "U1") (pin "81") (pinfunction "+5V(INPUT)_81") (pintype "power_in"))
      (node (ref "U1") (pin "83") (pinfunction "+5V(INPUT)_83") (pintype "power_in"))
      (node (ref "U1") (pin "85") (pinfunction "+5V(INPUT)_85") (pintype "power_in"))
      (node (ref "U1") (pin "87") (pinfunction "+5V(INPUT)_87") (pintype "power_in"))
    )
    (net (code "2") (name "/+12 V") (class "Default")
      (node (ref "B13") (pin "2") (pinfunction "VIN_2") (pintype "passive"))
      (node (ref "B13") (pin "3") (pinfunction "EN_3") (pintype "passive"))
      (node (ref "B2") (pin "1") (pinfunction "S_1_1") (pintype "passive"))
      (node (ref "C1") (pin "1") (pinfunction "1_1") (pintype "passive"))
      (node (ref "C2") (pin "2") (pinfunction "2_2") (pintype "passive"))
      (node (ref "C27") (pin "2") (pinfunction "2_2") (pintype "passive"))
      (node (ref "C28") (pin "2") (pinfunction "2_2") (pintype "passive"))
      (node (ref "C29") (pin "2") (pinfunction "2_2") (pintype "passive"))
      (node (ref "C30") (pin "2") (pinfunction "2_2") (pintype "passive"))
      (node (ref "C31") (pin "2") (pinfunction "2_2") (pintype "passive"))
      (node (ref "C32") (pin "2") (pinfunction "2_2") (pintype "passive"))
      (node (ref "D1") (pin "3") (pinfunction "K_3") (pintype "passive"))
      (node (ref "P1") (pin "4") (pinfunction "4_4") (pintype "passive"))
      (node (ref "P5") (pin "2") (pinfunction "2_2") (pintype "passive"))
    )
    (net (code "3") (name "/1.8 V") (class "Default")
      (node (ref "R6") (pin "1") (pinfunction "1_1") (pintype "passive"))
      (node (ref "U1") (pin "88") (pinfunction "CM4_1.8V(OUTPUT)_88") (pintype "power_in"))
      (node (ref "U1") (pin "90") (pinfunction "CM4_1.8V(OUTPUT)_90") (pintype "power_in"))
    )
    (net (code "4") (name "/3.3 V") (class "Default")
      (node (ref "B11") (pin "1") (pinfunction "VCC_1") (pintype "passive"))
      (node (ref "B6") (pin "4") (pinfunction "EN~{/}EN_4") (pintype "passive"))
      (node (ref "B7") (pin "3") (pinfunction "VDD_3") (pintype "passive"))
      (node (ref "B8") (pin "5") (pinfunction "VCC_5") (pintype "passive"))
      (node (ref "B9") (pin "10") (pinfunction "VDDA33_2_10") (pintype "passive"))
      (node (ref "B9") (pin "15") (pinfunction "VDD33_1_15") (pintype "passive"))
      (node (ref "B9") (pin "23") (pinfunction "VDD33_2_23") (pintype "passive"))
      (node (ref "B9") (pin "27") (pinfunction "VBUS_DET_27") (pintype "passive"))
      (node (ref "B9") (pin "29") (pinfunction "VDDA33_3_29") (pintype "passive"))
      (node (ref "B9") (pin "36") (pinfunction "VDDA33_4_36") (pintype "passive"))
      (node (ref "B9") (pin "5") (pinfunction "VDDA33_1_5") (pintype "passive"))
      (node (ref "C10") (pin "2") (pinfunction "2_2") (pintype "passive"))
      (node (ref "C11") (pin "2") (pinfunction "2_2") (pintype "passive"))
      (node (ref "C12") (pin "1") (pinfunction "1_1") (pintype "passive"))
      (node (ref "C13") (pin "1") (pinfunction "1_1") (pintype "passive"))
      (node (ref "C14") (pin "1") (pinfunction "1_1") (pintype "passive"))
      (node (ref "C15") (pin "1") (pinfunction "1_1") (pintype "passive"))
      (node (ref "C16") (pin "1") (pinfunction "1_1") (pintype "passive"))
      (node (ref "C17") (pin "1") (pinfunction "1_1") (pintype "passive"))
      (node (ref "C9") (pin "2") (pinfunction "2_2") (pintype "passive"))
      (node (ref "D2") (pin "2") (pinfunction "A2_2") (pintype "passive"))
      (node (ref "D3") (pin "2") (pinfunction "A2_2") (pintype "passive"))
      (node (ref "D4") (pin "2") (pinfunction "A2_2") (pintype "passive"))
      (node (ref "J1") (pin "1") (pinfunction "1_1") (pintype "passive"))
      (node (ref "J1") (pin "17") (pinfunction "17_17") (pintype "passive"))
      (node (ref "J2") (pin "15") (pinfunction "GREEN_A_15") (pintype "passive"))
      (node (ref "J2") (pin "17") (pinfunction "YELLOW_A_17") (pintype "passive"))
      (node (ref "R11") (pin "2") (pinfunction "2_2") (pintype "passive"))
      (node (ref "R5") (pin "1") (pinfunction "1_1") (pintype "passive"))
      (node (ref "R7") (pin "2") (pinfunction "2_2") (pintype "passive"))
      (node (ref "R8") (pin "2") (pinfunction "2_2") (pintype "passive"))
      (node (ref "U1") (pin "84") (pinfunction "CM4_3.3V(OUTPUT)_84") (pintype "power_in"))
      (node (ref "U1") (pin "86") (pinfunction "CM4_3.3V(OUTPUT)_86") (pintype "power_in"))
    )
    (net (code "6") (name "/AIN0") (class "Default")
      (node (ref "P6") (pin "5") (pinfunction "5_5") (pintype "passive"))
      (node (ref "U1") (pin "96") (pinfunction "ANALOGIP0_96") (pintype "input"))
    )
    (net (code "7") (name "/AIN1") (class "Default")
      (node (ref "P6") (pin "6") (pinfunction "6_6") (pintype "passive"))
      (node (ref "U1") (pin "94") (pinfunction "ANALOGIP1_94") (pintype "input"))
    )
    (net (code "8") (name "/BT_DIS") (class "Default")
      (node (ref "P3") (pin "3") (pinfunction "3_3") (pintype "passive"))
      (node (ref "P4") (pin "3") (pinfunction "3_3") (pintype "passive"))
      (node (ref "U1") (pin "91") (pinfunction "BT_~{DISABLE}_91") (pintype "input"))
    )
    (net (code "9") (name "/EEPROM_WP") (class "Default")
      (node (ref "P6") (pin "4") (pinfunction "4_4") (pintype "passive"))
      (node (ref "U1") (pin "20") (pinfunction "EEPROM_~{WP}_20") (pintype "bidirectional"))
    )
    (net (code "10") (name "/ETH_LED G") (class "Default")
      (node (ref "R3") (pin "2") (pinfunction "2_2") (pintype "passive"))
      (node (ref "U1") (pin "17") (pinfunction "ETHERNET_~{LED2}_17") (pintype "output"))
    )
    (net (code "11") (name "/ETH_LED Y") (class "Default")
      (node (ref "R4") (pin "2") (pinfunction "2_2") (pintype "passive"))
      (node (ref "U1") (pin "15") (pinfunction "ETHERNET_~{LED3}_15") (pintype "output"))
    )
    (net (code "12") (name "/EXTRST") (class "Default")
      (node (ref "B9") (pin "26") (pinfunction "RESET_N_26") (pintype "passive"))
      (node (ref "U1") (pin "100") (pinfunction "~{EXTRST}_100") (pintype "output"))
    )
    (net (code "13") (name "/GLOBAL_EN") (class "Default")
      (node (ref "B5") (pin "4") (pinfunction "Y_4") (pintype "passive"))
      (node (ref "P6") (pin "14") (pinfunction "14_14") (pintype "passive"))
      (node (ref "U1") (pin "99") (pinfunction "GLOBAL_EN_99") (pintype "input"))
    )
    (net (code "14") (name "/GPIO2") (class "Default")
      (node (ref "J1") (pin "3") (pinfunction "3_3") (pintype "passive"))
      (node (ref "U1") (pin "58") (pinfunction "GPIO2_58") (pintype "bidirectional"))
    )
    (net (code "15") (name "/GPIO3") (class "Default")
      (node (ref "J1") (pin "5") (pinfunction "5_5") (pintype "passive"))
      (node (ref "U1") (pin "56") (pinfunction "GPIO3_56") (pintype "bidirectional"))
    )
    (net (code "16") (name "/GPIO4") (class "Default")
      (node (ref "J1") (pin "7") (pinfunction "7_7") (pintype "passive"))
      (node (ref "U1") (pin "54") (pinfunction "GPIO4_54") (pintype "bidirectional"))
    )
    (net (code "17") (name "/GPIO5") (class "Default")
      (node (ref "J1") (pin "29") (pinfunction "29_29") (pintype "passive"))
      (node (ref "U1") (pin "34") (pinfunction "GPIO5_34") (pintype "bidirectional"))
    )
    (net (code "18") (name "/GPIO6") (class "Default")
      (node (ref "J1") (pin "31") (pinfunction "31_31") (pintype "passive"))
      (node (ref "U1") (pin "30") (pinfunction "GPIO6_30") (pintype "bidirectional"))
    )
    (net (code "19") (name "/GPIO7") (class "Default")
      (node (ref "J1") (pin "26") (pinfunction "26_26") (pintype "passive"))
      (node (ref "U1") (pin "37") (pinfunction "GPIO7_37") (pintype "bidirectional"))
    )
    (net (code "20") (name "/GPIO8") (class "Default")
      (node (ref "J1") (pin "24") (pinfunction "24_24") (pintype "passive"))
      (node (ref "U1") (pin "39") (pinfunction "GPIO8_39") (pintype "bidirectional"))
    )
    (net (code "21") (name "/GPIO9") (class "Default")
      (node (ref "J1") (pin "21") (pinfunction "21_21") (pintype "passive"))
      (node (ref "U1") (pin "40") (pinfunction "GPIO9_40") (pintype "bidirectional"))
    )
    (net (code "22") (name "/GPIO10") (class "Default")
      (node (ref "J1") (pin "19") (pinfunction "19_19") (pintype "passive"))
      (node (ref "U1") (pin "44") (pinfunction "GPIO10_44") (pintype "bidirectional"))
    )
    (net (code "23") (name "/GPIO11") (class "Default")
      (node (ref "J1") (pin "23") (pinfunction "23_23") (pintype "passive"))
      (node (ref "U1") (pin "38") (pinfunction "GPIO11_38") (pintype "bidirectional"))
    )
    (net (code "24") (name "/GPIO12") (class "Default")
      (node (ref "J1") (pin "32") (pinfunction "32_32") (pintype "passive"))
      (node (ref "U1") (pin "31") (pinfunction "GPIO12_31") (pintype "bidirectional"))
    )
    (net (code "25") (name "/GPIO13") (class "Default")
      (node (ref "J1") (pin "33") (pinfunction "33_33") (pintype "passive"))
      (node (ref "U1") (pin "28") (pinfunction "GPIO13_28") (pintype "bidirectional"))
    )
    (net (code "26") (name "/GPIO14") (class "Default")
      (node (ref "J1") (pin "8") (pinfunction "8_8") (pintype "passive"))
      (node (ref "U1") (pin "55") (pinfunction "GPIO14_55") (pintype "bidirectional"))
    )
    (net (code "27") (name "/GPIO15") (class "Default")
      (node (ref "J1") (pin "10") (pinfunction "10_10") (pintype "passive"))
      (node (ref "U1") (pin "51") (pinfunction "GPIO15_51") (pintype "bidirectional"))
    )
    (net (code "28") (name "/GPIO16") (class "Default")
      (node (ref "J1") (pin "36") (pinfunction "36_36") (pintype "passive"))
      (node (ref "U1") (pin "29") (pinfunction "GPIO16_29") (pintype "bidirectional"))
    )
    (net (code "29") (name "/GPIO17") (class "Default")
      (node (ref "J1") (pin "11") (pinfunction "11_11") (pintype "passive"))
      (node (ref "U1") (pin "50") (pinfunction "GPIO17_50") (pintype "bidirectional"))
    )
    (net (code "30") (name "/GPIO18") (class "Default")
      (node (ref "J1") (pin "12") (pinfunction "12_12") (pintype "passive"))
      (node (ref "U1") (pin "49") (pinfunction "GPIO18_49") (pintype "bidirectional"))
    )
    (net (code "31") (name "/GPIO19") (class "Default")
      (node (ref "J1") (pin "35") (pinfunction "35_35") (pintype "passive"))
      (node (ref "U1") (pin "26") (pinfunction "GPIO19_26") (pintype "bidirectional"))
    )
    (net (code "32") (name "/GPIO20") (class "Default")
      (node (ref "J1") (pin "38") (pinfunction "38_38") (pintype "passive"))
      (node (ref "U1") (pin "27") (pinfunction "GPIO20_27") (pintype "bidirectional"))
    )
    (net (code "33") (name "/GPIO21") (class "Default")
      (node (ref "J1") (pin "40") (pinfunction "40_40") (pintype "passive"))
      (node (ref "U1") (pin "25") (pinfunction "GPIO21_25") (pintype "bidirectional"))
    )
    (net (code "34") (name "/GPIO22") (class "Default")
      (node (ref "J1") (pin "15") (pinfunction "15_15") (pintype "passive"))
      (node (ref "U1") (pin "46") (pinfunction "GPIO22_46") (pintype "bidirectional"))
    )
    (net (code "35") (name "/GPIO23") (class "Default")
      (node (ref "J1") (pin "16") (pinfunction "16_16") (pintype "passive"))
      (node (ref "U1") (pin "47") (pinfunction "GPIO23_47") (pintype "bidirectional"))
    )
    (net (code "36") (name "/GPIO24") (class "Default")
      (node (ref "J1") (pin "18") (pinfunction "18_18") (pintype "passive"))
      (node (ref "U1") (pin "45") (pinfunction "GPIO24_45") (pintype "bidirectional"))
    )
    (net (code "37") (name "/GPIO25") (class "Default")
      (node (ref "J1") (pin "22") (pinfunction "22_22") (pintype "passive"))
      (node (ref "U1") (pin "41") (pinfunction "GPIO25_41") (pintype "bidirectional"))
    )
    (net (code "38") (name "/GPIO26") (class "Default")
      (node (ref "J1") (pin "37") (pinfunction "37_37") (pintype "passive"))
      (node (ref "U1") (pin "24") (pinfunction "GPIO26_24") (pintype "bidirectional"))
    )
    (net (code "39") (name "/GPIO27") (class "Default")
      (node (ref "J1") (pin "13") (pinfunction "13_13") (pintype "passive"))
      (node (ref "U1") (pin "48") (pinfunction "GPIO27_48") (pintype "bidirectional"))
    )
    (net (code "40") (name "/GPIO_VREF") (class "Default")
      (node (ref "R5") (pin "2") (pinfunction "2_2") (pintype "passive"))
      (node (ref "R6") (pin "2") (pinfunction "2_2") (pintype "passive"))
      (node (ref "U1") (pin "78") (pinfunction "GPIO_VREF_78") (pintype "power_in"))
    )
    (net (code "41") (name "/HD1_N") (class "Default")
      (node (ref "B9") (pin "1") (pinfunction "USBDM_DN_1_/PRT_DIS_M1_1") (pintype "passive"))
      (node (ref "J6") (pin "2") (pinfunction "D-`_2") (pintype "passive"))
    )
    (net (code "42") (name "/HD1_P") (class "Default")
      (node (ref "B9") (pin "2") (pinfunction "USBDP_DM/PRT_DIS_P1_2") (pintype "passive"))
      (node (ref "J6") (pin "3") (pinfunction "D+`_3") (pintype "passive"))
    )
    (net (code "43") (name "/HD2_N") (class "Default")
      (node (ref "B9") (pin "3") (pinfunction "USBDM_DN2/PRT_DIS_M2_3") (pintype "passive"))
      (node (ref "J6") (pin "6") (pinfunction "D-_6") (pintype "passive"))
    )
    (net (code "44") (name "/HD2_P") (class "Default")
      (node (ref "B9") (pin "4") (pinfunction "USBDP_DN2/PR_T_D1S_P2_4") (pintype "passive"))
      (node (ref "J6") (pin "7") (pinfunction "D+_7") (pintype "passive"))
    )
    (net (code "45") (name "/HD3_N") (class "Default")
      (node (ref "B9") (pin "6") (pinfunction "NC_1_6") (pintype "passive"))
      (node (ref "P7") (pin "3") (pinfunction "3_3") (pintype "passive"))
    )
    (net (code "46") (name "/HD3_P") (class "Default")
      (node (ref "B9") (pin "7") (pinfunction "NC_2_7") (pintype "passive"))
      (node (ref "P7") (pin "5") (pinfunction "5_5") (pintype "passive"))
    )
    (net (code "47") (name "/HD4_N") (class "Default")
      (node (ref "B9") (pin "8") (pinfunction "NC_3_8") (pintype "passive"))
      (node (ref "P7") (pin "6") (pinfunction "6_6") (pintype "passive"))
    )
    (net (code "48") (name "/HD4_P") (class "Default")
      (node (ref "B9") (pin "9") (pinfunction "NC_4_9") (pintype "passive"))
      (node (ref "P7") (pin "4") (pinfunction "4_4") (pintype "passive"))
    )
    (net (code "49") (name "/ID_SC") (class "Default")
      (node (ref "J1") (pin "28") (pinfunction "28_28") (pintype "passive"))
      (node (ref "U1") (pin "35") (pinfunction "ID_SC_35") (pintype "bidirectional"))
    )
    (net (code "50") (name "/ID_SD") (class "Default")
      (node (ref "J1") (pin "27") (pinfunction "27_27") (pintype "passive"))
      (node (ref "U1") (pin "36") (pinfunction "ID_SD_36") (pintype "bidirectional"))
    )
    (net (code "51") (name "/PLL") (class "Default")
      (node (ref "B9") (pin "33") (pinfunction "XTALIN/CLKIN_33") (pintype "passive"))
      (node (ref "C18") (pin "1") (pinfunction "1_1") (pintype "passive"))
      (node (ref "Y2") (pin "1") (pinfunction "1_1") (pintype "passive"))
    )
    (net (code "52") (name "/PWR1") (class "Default")
      (node (ref "B14") (pin "3") (pinfunction "EN_3") (pintype "passive"))
      (node (ref "B9") (pin "12") (pinfunction "PRTPWR1/BC_EN1_12") (pintype "passive"))
    )
    (net (code "53") (name "/PWR_LED") (class "Default")
      (node (ref "B8") (pin "2") (pinfunction "A_2") (pintype "passive"))
      (node (ref "U1") (pin "95") (pinfunction "PI_LED_~{PWR}_95") (pintype "output"))
    )
    (net (code "54") (name "/RIBOOT") (class "Default")
      (node (ref "P6") (pin "2") (pinfunction "2_2") (pintype "passive"))
      (node (ref "U1") (pin "93") (pinfunction "~{RPIBOOT}_93") (pintype "input"))
    )
    (net (code "55") (name "/RUN_PG") (class "Default")
      (node (ref "B10") (pin "2") (pinfunction "A_2") (pintype "passive"))
      (node (ref "U1") (pin "92") (pinfunction "RUN_PG_92") (pintype "bidirectional"))
    )
    (net (code "56") (name "/SCL0") (class "Default")
      (node (ref "B7") (pin "2") (pinfunction "SMCLK_2") (pintype "passive"))
      (node (ref "U1") (pin "80") (pinfunction "SCL0_80") (pintype "input"))
    )
    (net (code "57") (name "/SDA0") (class "Default")
      (node (ref "B7") (pin "1") (pinfunction "SMDATA_1") (pintype "passive"))
      (node (ref "U1") (pin "82") (pinfunction "SDA0_82") (pintype "bidirectional"))
    )
    (net (code "58") (name "/SD_CLK") (class "Default")
      (node (ref "J4") (pin "5") (pinfunction "CLK_5") (pintype "passive"))
      (node (ref "U1") (pin "57") (pinfunction "SD_CLK_57") (pintype "bidirectional"))
    )
    (net (code "59") (name "/SD_CMD") (class "Default")
      (node (ref "J4") (pin "3") (pinfunction "CMD_3") (pintype "passive"))
      (node (ref "U1") (pin "62") (pinfunction "SD_CMD_62") (pintype "input"))
    )
    (net (code "60") (name "/SD_DAT0") (class "Default")
      (node (ref "J4") (pin "7") (pinfunction "DAT0_7") (pintype "passive"))
      (node (ref "U1") (pin "63") (pinfunction "SD_DAT0_63") (pintype "bidirectional"))
    )
    (net (code "61") (name "/SD_DAT1") (class "Default")
      (node (ref "J4") (pin "8") (pinfunction "DAT1_8") (pintype "passive"))
      (node (ref "U1") (pin "67") (pinfunction "SD_DAT1_67") (pintype "bidirectional"))
    )
    (net (code "62") (name "/SD_DAT2") (class "Default")
      (node (ref "J4") (pin "1") (pinfunction "DAT2_1") (pintype "passive"))
      (node (ref "U1") (pin "69") (pinfunction "SD_DAT2_69") (pintype "bidirectional"))
    )
    (net (code "63") (name "/SD_DAT3") (class "Default")
      (node (ref "J4") (pin "2") (pinfunction "CD/DAT3_2") (pintype "passive"))
      (node (ref "U1") (pin "61") (pinfunction "SD_DAT3_61") (pintype "bidirectional"))
    )
    (net (code "64") (name "/SD_PWR_ON") (class "Default")
      (node (ref "B6") (pin "1") (pinfunction "VOUT_1") (pintype "passive"))
      (node (ref "B6") (pin "5") (pinfunction "VIN_5") (pintype "passive"))
      (node (ref "R8") (pin "1") (pinfunction "1_1") (pintype "passive"))
      (node (ref "U1") (pin "75") (pinfunction "SD_PWR_ON_75") (pintype "output"))
    )
    (net (code "65") (name "/SYNC_IN") (class "Default")
      (node (ref "P6") (pin "8") (pinfunction "8_8") (pintype "passive"))
      (node (ref "U1") (pin "16") (pinfunction "ETHERNET_SYNC_IN_16") (pintype "input"))
    )
    (net (code "66") (name "/SYNC_OUT") (class "Default")
      (node (ref "P6") (pin "9") (pinfunction "9_9") (pintype "passive"))
      (node (ref "U1") (pin "18") (pinfunction "ETHERNET_SYNC_OUT_18") (pintype "output"))
    )
    (net (code "67") (name "/TR0_TAP") (class "Default")
      (node (ref "J2") (pin "11") (pinfunction "VC1_11") (pintype "passive"))
      (node (ref "P2") (pin "3") (pinfunction "3_3") (pintype "passive"))
    )
    (net (code "68") (name "/TR1_TAP") (class "Default")
      (node (ref "J2") (pin "12") (pinfunction "VC2_12") (pintype "passive"))
      (node (ref "P2") (pin "1") (pinfunction "1_1") (pintype "passive"))
    )
    (net (code "69") (name "/TR2_TAP") (class "Default")
      (node (ref "J2") (pin "13") (pinfunction "VC3_13") (pintype "passive"))
      (node (ref "P2") (pin "2") (pinfunction "2_2") (pintype "passive"))
    )
    (net (code "70") (name "/TR3_TAP") (class "Default")
      (node (ref "J2") (pin "14") (pinfunction "VC4_14") (pintype "passive"))
      (node (ref "P2") (pin "4") (pinfunction "4_4") (pintype "passive"))
    )
    (net (code "71") (name "/TRD0_N") (class "Default")
      (node (ref "B3") (pin "4") (pinfunction "D2+_4") (pintype "passive"))
      (node (ref "J2") (pin "2") (pinfunction "TD1-_2") (pintype "passive"))
      (node (ref "U1") (pin "10") (pinfunction "ETHERNET_PAIR0_N_10") (pintype "bidirectional"))
    )
    (net (code "72") (name "/TRD0_P") (class "Default")
      (node (ref "B3") (pin "5") (pinfunction "D2-_5") (pintype "passive"))
      (node (ref "J2") (pin "1") (pinfunction "TD1+_1") (pintype "passive"))
      (node (ref "U1") (pin "12") (pinfunction "ETHERNET_PAIR0_P_12") (pintype "bidirectional"))
    )
    (net (code "73") (name "/TRD1_N") (class "Default")
      (node (ref "B3") (pin "2") (pinfunction "D1-_2") (pintype "passive"))
      (node (ref "J2") (pin "6") (pinfunction "TD2-_3_6") (pintype "passive"))
      (node (ref "U1") (pin "6") (pinfunction "ETHERNET_PAIR1_N_6") (pintype "bidirectional"))
    )
    (net (code "74") (name "/TRD1_P") (class "Default")
      (node (ref "B3") (pin "1") (pinfunction "D1+_1") (pintype "passive"))
      (node (ref "J2") (pin "3") (pinfunction "TD2+_3") (pintype "passive"))
      (node (ref "U1") (pin "4") (pinfunction "ETHERNET_PAIR1_P_4") (pintype "bidirectional"))
    )
    (net (code "75") (name "/TRD2_N") (class "Default")
      (node (ref "B1") (pin "4") (pinfunction "D2+_4") (pintype "passive"))
      (node (ref "J2") (pin "8") (pinfunction "TD3-_8") (pintype "passive"))
      (node (ref "U1") (pin "9") (pinfunction "ETHERNET_PAIR2_N_9") (pintype "bidirectional"))
    )
    (net (code "76") (name "/TRD2_P") (class "Default")
      (node (ref "B1") (pin "5") (pinfunction "D2-_5") (pintype "passive"))
      (node (ref "J2") (pin "7") (pinfunction "TD3+_7") (pintype "passive"))
      (node (ref "U1") (pin "11") (pinfunction "ETHERNET_PAIR2_P_11") (pintype "bidirectional"))
    )
    (net (code "77") (name "/TRD3_N") (class "Default")
      (node (ref "B1") (pin "2") (pinfunction "D1-_2") (pintype "passive"))
      (node (ref "J2") (pin "10") (pinfunction "TD4-_10") (pintype "passive"))
      (node (ref "U1") (pin "5") (pinfunction "ETHERNET_PAIR3_N_5") (pintype "bidirectional"))
    )
    (net (code "78") (name "/TRD3_P") (class "Default")
      (node (ref "B1") (pin "1") (pinfunction "D1+_1") (pintype "passive"))
      (node (ref "J2") (pin "9") (pinfunction "TD4+_9") (pintype "passive"))
      (node (ref "U1") (pin "3") (pinfunction "ETHERNET_PAIR3_P_3") (pintype "bidirectional"))
    )
    (net (code "79") (name "/TV_OUT") (class "Default")
      (node (ref "P6") (pin "11") (pinfunction "11_11") (pintype "passive"))
    )
    (net (code "80") (name "/USBD_N") (class "Default")
      (node (ref "B11") (pin "8") (pinfunction "HSD2-_8") (pintype "passive"))
      (node (ref "B12") (pin "4") (pinfunction "D2+_4") (pintype "passive"))
      (node (ref "J5") (pin "2") (pinfunction "D-_2") (pintype "bidirectional"))
    )
    (net (code "81") (name "/USBD_P") (class "Default")
      (node (ref "B11") (pin "9") (pinfunction "HSD2+_9") (pintype "passive"))
      (node (ref "B12") (pin "5") (pinfunction "D2-_5") (pintype "passive"))
      (node (ref "J5") (pin "3") (pinfunction "D+_3") (pintype "bidirectional"))
    )
    (net (code "82") (name "/USBH_N") (class "Default")
      (node (ref "B11") (pin "6") (pinfunction "HSD1-_6") (pintype "passive"))
      (node (ref "B9") (pin "30") (pinfunction "USBDM_UP_30") (pintype "passive"))
    )
    (net (code "83") (name "/USBH_P") (class "Default")
      (node (ref "B11") (pin "7") (pinfunction "HSD1+_7") (pintype "passive"))
      (node (ref "B9") (pin "31") (pinfunction "USBDP_UP_31") (pintype "passive"))
    )
    (net (code "84") (name "/USBOTG") (class "Default")
      (node (ref "B11") (pin "2") (pinfunction "SEL_2") (pintype "passive"))
      (node (ref "R14") (pin "2") (pinfunction "2_2") (pintype "passive"))
      (node (ref "R15") (pin "1") (pinfunction "1_1") (pintype "passive"))
    )
    (net (code "85") (name "/VBUS") (class "Default")
      (node (ref "J6") (pin "1") (pinfunction "VBUS`_1") (pintype "power_in"))
      (node (ref "J6") (pin "5") (pinfunction "VBUS_5") (pintype "power_in"))
      (node (ref "P7") (pin "1") (pinfunction "1_1") (pintype "passive"))
      (node (ref "P7") (pin "2") (pinfunction "2_2") (pintype "passive"))
    )
    (net (code "86") (name "/WL_DIS") (class "Default")
      (node (ref "P3") (pin "1") (pinfunction "1_1") (pintype "passive"))
      (node (ref "P4") (pin "1") (pinfunction "1_1") (pintype "passive"))
      (node (ref "U1") (pin "89") (pinfunction "WL_~{DISABLE}_89") (pintype "input"))
    )
    (net (code "87") (name "/XTAL") (class "Default")
      (node (ref "B9") (pin "32") (pinfunction "XTALOUT_32") (pintype "passive"))
      (node (ref "C19") (pin "1") (pinfunction "1_1") (pintype "passive"))
      (node (ref "Y2") (pin "2") (pinfunction "2_2") (pintype "passive"))
    )
    (net (code "88") (name "/nOCS1") (class "Default")
      (node (ref "B14") (pin "4") (pinfunction "FAULT_4") (pintype "passive"))
      (node (ref "B9") (pin "13") (pinfunction "OCS_N1_13") (pintype "passive"))
      (node (ref "B9") (pin "17") (pinfunction "OCS_N2_17") (pintype "passive"))
      (node (ref "B9") (pin "19") (pinfunction "NC_6_19") (pintype "passive"))
      (node (ref "B9") (pin "21") (pinfunction "NC_8_21") (pintype "passive"))
    )
    (net (code "89") (name "/nRTC_INT") (class "Default")
      (node (ref "B4") (pin "3") (pinfunction "INT_3") (pintype "passive"))
      (node (ref "C7") (pin "2") (pinfunction "2_2") (pintype "passive"))
      (node (ref "R9") (pin "2") (pinfunction "2_2") (pintype "passive"))
    )
    (net (code "90") (name "GND") (class "Default")
      (node (ref "B1") (pin "3") (pinfunction "GND_1_3") (pintype "passive"))
      (node (ref "B10") (pin "3") (pinfunction "GND_3") (pintype "passive"))
      (node (ref "B11") (pin "10") (pinfunction "/OE_10") (pintype "passive"))
      (node (ref "B11") (pin "5") (pinfunction "GND_5") (pintype "passive"))
      (node (ref "B12") (pin "3") (pinfunction "GND_1_3") (pintype "passive"))
      (node (ref "B12") (pin "8") (pinfunction "GND_2_8") (pintype "passive"))
      (node (ref "B14") (pin "2") (pinfunction "GND_2") (pintype "passive"))
      (node (ref "B3") (pin "3") (pinfunction "GND_1_3") (pintype "passive"))
      (node (ref "B4") (pin "4") (pinfunction "VSS_4") (pintype "passive"))
      (node (ref "B6") (pin "2") (pinfunction "GND_2") (pintype "passive"))
      (node (ref "B7") (pin "4") (pinfunction "GND_4") (pintype "passive"))
      (node (ref "B8") (pin "3") (pinfunction "GND_3") (pintype "passive"))
      (node (ref "BT1") (pin "P1") (pinfunction "POS_P1") (pintype "passive"))
      (node (ref "BT1") (pin "P2") (pinfunction "POS_P2") (pintype "passive"))
      (node (ref "C10") (pin "1") (pinfunction "1_1") (pintype "passive"))
      (node (ref "C11") (pin "1") (pinfunction "1_1") (pintype "passive"))
      (node (ref "C12") (pin "2") (pinfunction "2_2") (pintype "passive"))
      (node (ref "C13") (pin "2") (pinfunction "2_2") (pintype "passive"))
      (node (ref "C14") (pin "2") (pinfunction "2_2") (pintype "passive"))
      (node (ref "C15") (pin "2") (pinfunction "2_2") (pintype "passive"))
      (node (ref "C16") (pin "2") (pinfunction "2_2") (pintype "passive"))
      (node (ref "C17") (pin "2") (pinfunction "2_2") (pintype "passive"))
      (node (ref "C18") (pin "2") (pinfunction "2_2") (pintype "passive"))
      (node (ref "C19") (pin "2") (pinfunction "2_2") (pintype "passive"))
      (node (ref "C2") (pin "1") (pinfunction "1_1") (pintype "passive"))
      (node (ref "C20") (pin "2") (pinfunction "2_2") (pintype "passive"))
      (node (ref "C22") (pin "1") (pinfunction "1_1") (pintype "passive"))
      (node (ref "C23") (pin "1") (pinfunction "1_1") (pintype "passive"))
      (node (ref "C24") (pin "1") (pinfunction "1_1") (pintype "passive"))
      (node (ref "C25") (pin "1") (pinfunction "1_1") (pintype "passive"))
      (node (ref "C27") (pin "1") (pinfunction "1_1") (pintype "passive"))
      (node (ref "C28") (pin "1") (pinfunction "1_1") (pintype "passive"))
      (node (ref "C29") (pin "1") (pinfunction "1_1") (pintype "passive"))
      (node (ref "C3") (pin "1") (pinfunction "1_1") (pintype "passive"))
      (node (ref "C30") (pin "1") (pinfunction "1_1") (pintype "passive"))
      (node (ref "C31") (pin "1") (pinfunction "1_1") (pintype "passive"))
      (node (ref "C32") (pin "1") (pinfunction "1_1") (pintype "passive"))
      (node (ref "C33") (pin "1") (pinfunction "1_1") (pintype "passive"))
      (node (ref "C34") (pin "1") (pinfunction "1_1") (pintype "passive"))
      (node (ref "C35") (pin "2") (pinfunction "2_2") (pintype "passive"))
      (node (ref "C36") (pin "1") (pinfunction "1_1") (pintype "passive"))
      (node (ref "C37") (pin "1") (pinfunction "1_1") (pintype "passive"))
      (node (ref "C38") (pin "1") (pinfunction "1_1") (pintype "passive"))
      (node (ref "C39") (pin "1") (pinfunction "1_1") (pintype "passive"))
      (node (ref "C4") (pin "1") (pinfunction "1_1") (pintype "passive"))
      (node (ref "C40") (pin "1") (pinfunction "1_1") (pintype "passive"))
      (node (ref "C41") (pin "1") (pinfunction "1_1") (pintype "passive"))
      (node (ref "C5") (pin "1") (pinfunction "1_1") (pintype "passive"))
      (node (ref "C6") (pin "1") (pinfunction "1_1") (pintype "passive"))
      (node (ref "C8") (pin "1") (pinfunction "1_1") (pintype "passive"))
      (node (ref "C9") (pin "1") (pinfunction "1_1") (pintype "passive"))
      (node (ref "J1") (pin "14") (pinfunction "14_14") (pintype "passive"))
      (node (ref "J1") (pin "20") (pinfunction "20_20") (pintype "passive"))
      (node (ref "J1") (pin "25") (pinfunction "25_25") (pintype "passive"))
      (node (ref "J1") (pin "30") (pinfunction "30_30") (pintype "passive"))
      (node (ref "J1") (pin "34") (pinfunction "34_34") (pintype "passive"))
      (node (ref "J1") (pin "39") (pinfunction "39_39") (pintype "passive"))
      (node (ref "J1") (pin "6") (pinfunction "6_6") (pintype "passive"))
      (node (ref "J1") (pin "9") (pinfunction "9_9") (pintype "passive"))
      (node (ref "J2") (pin "MH1") (pinfunction "MH1_MH1") (pintype "passive"))
      (node (ref "J2") (pin "MH2") (pinfunction "MH2_MH2") (pintype "passive"))
      (node (ref "J3") (pin "2") (pinfunction "2_2") (pintype "passive"))
      (node (ref "J3") (pin "3") (pinfunction "3_3") (pintype "passive"))
      (node (ref "J4") (pin "6") (pinfunction "VSS_6") (pintype "passive"))
      (node (ref "J4") (pin "G1") (pinfunction "GND_G1") (pintype "passive"))
      (node (ref "J5") (pin "5") (pinfunction "GND_5") (pintype "power_in"))
      (node (ref "J5") (pin "S1") (pinfunction "SHIELD_S1") (pintype "passive"))
      (node (ref "J5") (pin "S2") (pinfunction "SHIELD_S2") (pintype "passive"))
      (node (ref "J5") (pin "S3") (pinfunction "SHIELD_S3") (pintype "passive"))
      (node (ref "J5") (pin "S4") (pinfunction "SHIELD_S4") (pintype "passive"))
      (node (ref "J6") (pin "4") (pinfunction "GND`_4") (pintype "power_in"))
      (node (ref "J6") (pin "8") (pinfunction "GND_8") (pintype "power_in"))
      (node (ref "P1") (pin "2") (pinfunction "2_2") (pintype "passive"))
      (node (ref "P1") (pin "3") (pinfunction "3_3") (pintype "passive"))
      (node (ref "P3") (pin "2") (pinfunction "2_2") (pintype "passive"))
      (node (ref "P4") (pin "2") (pinfunction "2_2") (pintype "passive"))
      (node (ref "P5") (pin "1") (pinfunction "1_1") (pintype "passive"))
      (node (ref "P6") (pin "1") (pinfunction "1_1") (pintype "passive"))
      (node (ref "P6") (pin "10") (pinfunction "10_10") (pintype "passive"))
      (node (ref "P6") (pin "12") (pinfunction "12_12") (pintype "passive"))
      (node (ref "P6") (pin "3") (pinfunction "3_3") (pintype "passive"))
      (node (ref "P6") (pin "7") (pinfunction "7_7") (pintype "passive"))
      (node (ref "P7") (pin "7") (pinfunction "7_7") (pintype "passive"))
      (node (ref "P7") (pin "8") (pinfunction "8_8") (pintype "passive"))
      (node (ref "R1") (pin "1") (pinfunction "1_1") (pintype "passive"))
      (node (ref "R13") (pin "1") (pinfunction "1_1") (pintype "passive"))
      (node (ref "R15") (pin "2") (pinfunction "2_2") (pintype "passive"))
      (node (ref "R19") (pin "1") (pinfunction "1_1") (pintype "passive"))
      (node (ref "R20") (pin "2") (pinfunction "2_2") (pintype "passive"))
      (node (ref "U1") (pin "1") (pinfunction "GND_1") (pintype "power_in"))
      (node (ref "U1") (pin "107") (pinfunction "GND_107") (pintype "power_in"))
      (node (ref "U1") (pin "108") (pinfunction "GND_108") (pintype "power_in"))
      (node (ref "U1") (pin "113") (pinfunction "GND_113") (pintype "power_in"))
      (node (ref "U1") (pin "114") (pinfunction "GND_114") (pintype "power_in"))
      (node (ref "U1") (pin "119") (pinfunction "GND_119") (pintype "power_in"))
      (node (ref "U1") (pin "120") (pinfunction "GND_120") (pintype "power_in"))
      (node (ref "U1") (pin "125") (pinfunction "GND_125") (pintype "power_in"))
      (node (ref "U1") (pin "126") (pinfunction "GND_126") (pintype "power_in"))
      (node (ref "U1") (pin "13") (pinfunction "GND_13") (pintype "power_in"))
      (node (ref "U1") (pin "131") (pinfunction "GND_131") (pintype "power_in"))
      (node (ref "U1") (pin "132") (pinfunction "GND_132") (pintype "power_in"))
      (node (ref "U1") (pin "137") (pinfunction "GND_137") (pintype "power_in"))
      (node (ref "U1") (pin "138") (pinfunction "GND_138") (pintype "power_in"))
      (node (ref "U1") (pin "14") (pinfunction "GND_14") (pintype "power_in"))
      (node (ref "U1") (pin "144") (pinfunction "GND_144") (pintype "power_in"))
      (node (ref "U1") (pin "150") (pinfunction "GND_150") (pintype "power_in"))
      (node (ref "U1") (pin "155") (pinfunction "GND_155") (pintype "power_in"))
      (node (ref "U1") (pin "156") (pinfunction "GND_156") (pintype "power_in"))
      (node (ref "U1") (pin "161") (pinfunction "GND_161") (pintype "power_in"))
      (node (ref "U1") (pin "162") (pinfunction "GND_162") (pintype "power_in"))
      (node (ref "U1") (pin "167") (pinfunction "GND_167") (pintype "power_in"))
      (node (ref "U1") (pin "168") (pinfunction "GND_168") (pintype "power_in"))
      (node (ref "U1") (pin "173") (pinfunction "GND_173") (pintype "power_in"))
      (node (ref "U1") (pin "174") (pinfunction "GND_174") (pintype "power_in"))
      (node (ref "U1") (pin "179") (pinfunction "GND_179") (pintype "power_in"))
      (node (ref "U1") (pin "180") (pinfunction "GND_180") (pintype "power_in"))
      (node (ref "U1") (pin "185") (pinfunction "GND_185") (pintype "power_in"))
      (node (ref "U1") (pin "186") (pinfunction "GND_186") (pintype "power_in"))
      (node (ref "U1") (pin "191") (pinfunction "GND_191") (pintype "power_in"))
      (node (ref "U1") (pin "192") (pinfunction "GND_192") (pintype "power_in"))
      (node (ref "U1") (pin "197") (pinfunction "GND_197") (pintype "power_in"))
      (node (ref "U1") (pin "198") (pinfunction "GND_198") (pintype "power_in"))
      (node (ref "U1") (pin "2") (pinfunction "GND_2") (pintype "power_in"))
      (node (ref "U1") (pin "22") (pinfunction "GND_22") (pintype "power_in"))
      (node (ref "U1") (pin "23") (pinfunction "GND_23") (pintype "power_in"))
      (node (ref "U1") (pin "32") (pinfunction "GND_32") (pintype "power_in"))
      (node (ref "U1") (pin "33") (pinfunction "GND_33") (pintype "power_in"))
      (node (ref "U1") (pin "42") (pinfunction "GND_42") (pintype "power_in"))
      (node (ref "U1") (pin "43") (pinfunction "GND_43") (pintype "power_in"))
      (node (ref "U1") (pin "52") (pinfunction "GND_52") (pintype "power_in"))
      (node (ref "U1") (pin "53") (pinfunction "GND_53") (pintype "power_in"))
      (node (ref "U1") (pin "59") (pinfunction "GND_59") (pintype "power_in"))
      (node (ref "U1") (pin "60") (pinfunction "GND_60") (pintype "power_in"))
      (node (ref "U1") (pin "65") (pinfunction "GND_65") (pintype "power_in"))
      (node (ref "U1") (pin "66") (pinfunction "GND_66") (pintype "power_in"))
      (node (ref "U1") (pin "7") (pinfunction "GND_7") (pintype "power_in"))
      (node (ref "U1") (pin "71") (pinfunction "GND_71") (pintype "power_in"))
      (node (ref "U1") (pin "74") (pinfunction "GND_74") (pintype "power_in"))
      (node (ref "U1") (pin "8") (pinfunction "GND_8") (pintype "power_in"))
      (node (ref "U1") (pin "98") (pinfunction "GND_98") (pintype "power_in"))
    )
    (net (code "91") (name "Net-(B2-D_1)") (class "Default")
      (node (ref "B2") (pin "5") (pinfunction "D_1_5") (pintype "passive"))
      (node (ref "C4") (pin "2") (pinfunction "2_2") (pintype "passive"))
      (node (ref "J3") (pin "1") (pinfunction "1_1") (pintype "passive"))
    )
    (net (code "92") (name "Net-(B2-G)") (class "Default")
      (node (ref "B2") (pin "4") (pinfunction "G_4") (pintype "passive"))
      (node (ref "C1") (pin "2") (pinfunction "2_2") (pintype "passive"))
      (node (ref "D1") (pin "1") (pinfunction "A_1") (pintype "passive"))
      (node (ref "R1") (pin "2") (pinfunction "2_2") (pintype "passive"))
    )
    (net (code "93") (name "Net-(B4-OSCI)") (class "Default")
      (node (ref "B4") (pin "1") (pinfunction "OSCI_1") (pintype "passive"))
      (node (ref "Y1") (pin "2") (pinfunction "2_2") (pintype "passive"))
    )
    (net (code "94") (name "Net-(B4-OSCO)") (class "Default")
      (node (ref "B4") (pin "2") (pinfunction "OSCO_2") (pintype "passive"))
      (node (ref "Y1") (pin "1") (pinfunction "1_1") (pintype "passive"))
    )
    (net (code "95") (name "Net-(B4-VDD)") (class "Default")
      (node (ref "B4") (pin "8") (pinfunction "VDD_8") (pintype "passive"))
      (node (ref "C5") (pin "2") (pinfunction "2_2") (pintype "passive"))
      (node (ref "D3") (pin "3") (pinfunction "COM_K_3") (pintype "passive"))
    )
    (net (code "96") (name "Net-(B5-A)") (class "Default")
      (node (ref "B5") (pin "2") (pinfunction "A_2") (pintype "passive"))
      (node (ref "C7") (pin "1") (pinfunction "1_1") (pintype "passive"))
      (node (ref "R10") (pin "2") (pinfunction "2_2") (pintype "passive"))
    )
    (net (code "97") (name "Net-(B7-PWM)") (class "Default")
      (node (ref "B7") (pin "5") (pinfunction "PWM_5") (pintype "passive"))
      (node (ref "P5") (pin "4") (pinfunction "4_4") (pintype "passive"))
    )
    (net (code "98") (name "Net-(B7-TACH)") (class "Default")
      (node (ref "B7") (pin "6") (pinfunction "TACH_6") (pintype "passive"))
      (node (ref "P5") (pin "3") (pinfunction "3_3") (pintype "passive"))
      (node (ref "R11") (pin "1") (pinfunction "1_1") (pintype "passive"))
    )
    (net (code "99") (name "Net-(B8-Y)") (class "Default")
      (node (ref "B8") (pin "4") (pinfunction "Y_4") (pintype "passive"))
      (node (ref "R12") (pin "1") (pinfunction "1_1") (pintype "passive"))
    )
    (net (code "100") (name "Net-(B9-RBIAS)") (class "Default")
      (node (ref "B9") (pin "35") (pinfunction "RBIAS_35") (pintype "passive"))
      (node (ref "R13") (pin "2") (pinfunction "2_2") (pintype "passive"))
    )
    (net (code "101") (name "Net-(B10-Y)") (class "Default")
      (node (ref "B10") (pin "4") (pinfunction "Y_4") (pintype "passive"))
      (node (ref "P6") (pin "13") (pinfunction "13_13") (pintype "passive"))
    )
    (net (code "102") (name "Net-(B13-BST)") (class "Default")
      (node (ref "B13") (pin "1") (pinfunction "BST_1") (pintype "passive"))
      (node (ref "C21") (pin "1") (pinfunction "1_1") (pintype "passive"))
    )
    (net (code "103") (name "Net-(B13-COMP)") (class "Default")
      (node (ref "B13") (pin "6") (pinfunction "COMP_6") (pintype "passive"))
      (node (ref "C34") (pin "2") (pinfunction "2_2") (pintype "passive"))
      (node (ref "R18") (pin "2") (pinfunction "2_2") (pintype "passive"))
    )
    (net (code "104") (name "Net-(B13-FB)") (class "Default")
      (node (ref "B13") (pin "5") (pinfunction "FB_5") (pintype "passive"))
      (node (ref "C26") (pin "1") (pinfunction "1_1") (pintype "passive"))
      (node (ref "R17") (pin "1") (pinfunction "1_1") (pintype "passive"))
      (node (ref "R19") (pin "2") (pinfunction "2_2") (pintype "passive"))
    )
    (net (code "105") (name "Net-(B13-SS)") (class "Default")
      (node (ref "B13") (pin "4") (pinfunction "SS_4") (pintype "passive"))
      (node (ref "C33") (pin "2") (pinfunction "2_2") (pintype "passive"))
    )
    (net (code "106") (name "Net-(B13-SW)") (class "Default")
      (node (ref "B13") (pin "8") (pinfunction "SW_8") (pintype "passive"))
      (node (ref "L1") (pin "1") (pinfunction "1_1") (pintype "passive"))
      (node (ref "R16") (pin "2") (pinfunction "2_2") (pintype "passive"))
    )
    (net (code "107") (name "Net-(B14-ILIM)") (class "Default")
      (node (ref "B14") (pin "5") (pinfunction "ILIM_5") (pintype "passive"))
      (node (ref "R20") (pin "1") (pinfunction "1_1") (pintype "passive"))
    )
    (net (code "108") (name "Net-(B14-OUT)") (class "Default")
      (node (ref "B14") (pin "6") (pinfunction "OUT_6") (pintype "passive"))
      (node (ref "C35") (pin "1") (pinfunction "1_1") (pintype "passive"))
      (node (ref "C37") (pin "2") (pinfunction "2_2") (pintype "passive"))
      (node (ref "C38") (pin "2") (pinfunction "2_2") (pintype "passive"))
      (node (ref "C39") (pin "2") (pinfunction "2_2") (pintype "passive"))
      (node (ref "C40") (pin "2") (pinfunction "2_2") (pintype "passive"))
    )
    (net (code "109") (name "Net-(BT1-NEG)") (class "Default")
      (node (ref "BT1") (pin "N") (pinfunction "NEG_N") (pintype "passive"))
      (node (ref "D3") (pin "1") (pinfunction "A1_1") (pintype "passive"))
    )
    (net (code "110") (name "Net-(C21-Pad2)") (class "Default")
      (node (ref "C21") (pin "2") (pinfunction "2_2") (pintype "passive"))
      (node (ref "R16") (pin "1") (pinfunction "1_1") (pintype "passive"))
    )
    (net (code "111") (name "Net-(C41-Pad2)") (class "Default")
      (node (ref "C41") (pin "2") (pinfunction "2_2") (pintype "passive"))
      (node (ref "R18") (pin "1") (pinfunction "1_1") (pintype "passive"))
    )
    (net (code "112") (name "Net-(D2-K2)") (class "Default")
      (node (ref "D2") (pin "1") (pinfunction "K2_1") (pintype "passive"))
      (node (ref "R2") (pin "2") (pinfunction "2_2") (pintype "passive"))
    )
    (net (code "113") (name "Net-(D4-K2)") (class "Default")
      (node (ref "D4") (pin "1") (pinfunction "K2_1") (pintype "passive"))
      (node (ref "R12") (pin "2") (pinfunction "2_2") (pintype "passive"))
    )
    (net (code "114") (name "Net-(J2-GREEN_K)") (class "Default")
      (node (ref "J2") (pin "16") (pinfunction "GREEN_K_16") (pintype "passive"))
      (node (ref "R3") (pin "1") (pinfunction "1_1") (pintype "passive"))
    )
    (net (code "115") (name "Net-(J2-TD2-_1)") (class "Default")
      (node (ref "C3") (pin "2") (pinfunction "2_2") (pintype "passive"))
      (node (ref "J2") (pin "4") (pinfunction "TD2-_1_4") (pintype "passive"))
      (node (ref "J2") (pin "5") (pinfunction "TD2-_2_5") (pintype "passive"))
    )
    (net (code "116") (name "Net-(J2-YELLOW_K)") (class "Default")
      (node (ref "J2") (pin "18") (pinfunction "YELLOW_K_18") (pintype "passive"))
      (node (ref "R4") (pin "1") (pinfunction "1_1") (pintype "passive"))
    )
    (net (code "117") (name "Net-(J4-CARD_DETECTION)") (class "Default")
      (node (ref "J4") (pin "CD1") (pinfunction "CARD_DETECTION_CD1") (pintype "passive"))
      (node (ref "R7") (pin "1") (pinfunction "1_1") (pintype "passive"))
    )
    (net (code "118") (name "Net-(J4-VDD)") (class "Default")
      (node (ref "C6") (pin "2") (pinfunction "2_2") (pintype "passive"))
      (node (ref "J4") (pin "4") (pinfunction "VDD_4") (pintype "passive"))
    )
    (net (code "119") (name "Net-(J5-VCC)") (class "Default")
      (node (ref "J5") (pin "1") (pinfunction "VCC_1") (pintype "power_in"))
      (node (ref "R14") (pin "1") (pinfunction "1_1") (pintype "passive"))
    )
    (net (code "120") (name "Net-(U1A-PI_~{LED}_ACTIVITY)") (class "Default")
      (node (ref "R2") (pin "1") (pinfunction "1_1") (pintype "passive"))
      (node (ref "U1") (pin "21") (pinfunction "PI_~{LED}_ACTIVITY_21") (pintype "bidirectional"))
    )
    (net (code "121") (name "unconnected-(B1-GND_2-Pad8)") (class "Default")
      (node (ref "B1") (pin "8") (pinfunction "GND_2_8") (pintype "passive"))
    )
    (net (code "122") (name "unconnected-(B1-N.C._1-Pad6)") (class "Default")
      (node (ref "B1") (pin "6") (pinfunction "N.C._1_6") (pintype "passive"))
    )
    (net (code "123") (name "unconnected-(B1-N.C._2-Pad7)") (class "Default")
      (node (ref "B1") (pin "7") (pinfunction "N.C._2_7") (pintype "passive"))
    )
    (net (code "124") (name "unconnected-(B1-N.C._3-Pad9)") (class "Default")
      (node (ref "B1") (pin "9") (pinfunction "N.C._3_9") (pintype "passive"))
    )
    (net (code "125") (name "unconnected-(B1-N.C._4-Pad10)") (class "Default")
      (node (ref "B1") (pin "10") (pinfunction "N.C._4_10") (pintype "passive"))
    )
    (net (code "126") (name "unconnected-(B2-D_2-Pad6)") (class "Default")
      (node (ref "B2") (pin "6") (pinfunction "D_2_6") (pintype "passive"))
    )
    (net (code "127") (name "unconnected-(B2-D_3-Pad7)") (class "Default")
      (node (ref "B2") (pin "7") (pinfunction "D_3_7") (pintype "passive"))
    )
    (net (code "128") (name "unconnected-(B2-D_4-Pad8)") (class "Default")
      (node (ref "B2") (pin "8") (pinfunction "D_4_8") (pintype "passive"))
    )
    (net (code "129") (name "unconnected-(B2-D_5-Pad9)") (class "Default")
      (node (ref "B2") (pin "9") (pinfunction "D_5_9") (pintype "passive"))
    )
    (net (code "130") (name "unconnected-(B2-S_2-Pad2)") (class "Default")
      (node (ref "B2") (pin "2") (pinfunction "S_2_2") (pintype "passive"))
    )
    (net (code "131") (name "unconnected-(B2-S_3-Pad3)") (class "Default")
      (node (ref "B2") (pin "3") (pinfunction "S_3_3") (pintype "passive"))
    )
    (net (code "132") (name "unconnected-(B3-GND_2-Pad8)") (class "Default")
      (node (ref "B3") (pin "8") (pinfunction "GND_2_8") (pintype "passive"))
    )
    (net (code "133") (name "unconnected-(B3-N.C._1-Pad6)") (class "Default")
      (node (ref "B3") (pin "6") (pinfunction "N.C._1_6") (pintype "passive"))
    )
    (net (code "134") (name "unconnected-(B3-N.C._2-Pad7)") (class "Default")
      (node (ref "B3") (pin "7") (pinfunction "N.C._2_7") (pintype "passive"))
    )
    (net (code "135") (name "unconnected-(B3-N.C._3-Pad9)") (class "Default")
      (node (ref "B3") (pin "9") (pinfunction "N.C._3_9") (pintype "passive"))
    )
    (net (code "136") (name "unconnected-(B3-N.C._4-Pad10)") (class "Default")
      (node (ref "B3") (pin "10") (pinfunction "N.C._4_10") (pintype "passive"))
    )
    (net (code "137") (name "unconnected-(B4-CLKOUT-Pad7)") (class "Default")
      (node (ref "B4") (pin "7") (pinfunction "CLKOUT_7") (pintype "passive"))
    )
    (net (code "138") (name "unconnected-(B4-SCL-Pad6)") (class "Default")
      (node (ref "B4") (pin "6") (pinfunction "SCL_6") (pintype "passive"))
    )
    (net (code "139") (name "unconnected-(B4-SDA-Pad5)") (class "Default")
      (node (ref "B4") (pin "5") (pinfunction "SDA_5") (pintype "passive"))
    )
    (net (code "140") (name "unconnected-(B5-GND-Pad3)") (class "Default")
      (node (ref "B5") (pin "3") (pinfunction "GND_3") (pintype "passive"))
    )
    (net (code "141") (name "unconnected-(B5-NC-Pad1)") (class "Default")
      (node (ref "B5") (pin "1") (pinfunction "NC_1") (pintype "passive"))
    )
    (net (code "142") (name "unconnected-(B6-FLG-Pad3)") (class "Default")
      (node (ref "B6") (pin "3") (pinfunction "FLG_3") (pintype "passive"))
    )
    (net (code "143") (name "unconnected-(B7-ALERT#-Pad8)") (class "Default")
      (node (ref "B7") (pin "8") (pinfunction "ALERT#_8") (pintype "passive"))
    )
    (net (code "144") (name "unconnected-(B7-CLK-Pad7)") (class "Default")
      (node (ref "B7") (pin "7") (pinfunction "CLK_7") (pintype "passive"))
    )
    (net (code "145") (name "unconnected-(B8-NC-Pad1)") (class "Default")
      (node (ref "B8") (pin "1") (pinfunction "NC_1") (pintype "passive"))
    )
    (net (code "146") (name "unconnected-(B9-CRFILT-Pad14)") (class "Default")
      (node (ref "B9") (pin "14") (pinfunction "CRFILT_14") (pintype "passive"))
    )
    (net (code "147") (name "unconnected-(B9-HS_IND{slash}CFG_SEL1-Pad25)") (class "Default")
      (node (ref "B9") (pin "25") (pinfunction "HS_IND/CFG_SEL1_25") (pintype "passive"))
    )
    (net (code "148") (name "unconnected-(B9-NAME-PadNUMBER)") (class "Default")
      (node (ref "B9") (pin "NUMBER") (pinfunction "NAME_NUMBER") (pintype "passive"))
    )
    (net (code "149") (name "unconnected-(B9-NC_5-Pad18)") (class "Default")
      (node (ref "B9") (pin "18") (pinfunction "NC_5_18") (pintype "passive"))
    )
    (net (code "150") (name "unconnected-(B9-NC_7-Pad20)") (class "Default")
      (node (ref "B9") (pin "20") (pinfunction "NC_7_20") (pintype "passive"))
    )
    (net (code "151") (name "unconnected-(B9-PLLFILT-Pad34)") (class "Default")
      (node (ref "B9") (pin "34") (pinfunction "PLLFILT_34") (pintype "passive"))
    )
    (net (code "152") (name "unconnected-(B9-PRTPWR2{slash}BC_EN2-Pad16)") (class "Default")
      (node (ref "B9") (pin "16") (pinfunction "PRTPWR2/BC_EN2_16") (pintype "passive"))
    )
    (net (code "153") (name "unconnected-(B9-SC_L{slash}SM_BCL_K{slash}C_FGSEL0-Pad24)") (class "Default")
      (node (ref "B9") (pin "24") (pinfunction "SC_L/SM_BCL_K/C_FGSEL0_24") (pintype "passive"))
    )
    (net (code "154") (name "unconnected-(B9-SDA{slash}SMBDATA{slash}NON_REM1-Pad22)") (class "Default")
      (node (ref "B9") (pin "22") (pinfunction "SDA/SMBDATA/NON_REM1_22") (pintype "passive"))
    )
    (net (code "155") (name "unconnected-(B9-SUSP_IND{slash}LOCAL_PWR{slash}NON_REM0-Pad28)") (class "Default")
      (node (ref "B9") (pin "28") (pinfunction "SUSP_IND/LOCAL_PWR/NON_REM0_28") (pintype "passive"))
    )
    (net (code "156") (name "unconnected-(B9-TEST-Pad11)") (class "Default")
      (node (ref "B9") (pin "11") (pinfunction "TEST_11") (pintype "passive"))
    )
    (net (code "157") (name "unconnected-(B10-NC-Pad1)") (class "Default")
      (node (ref "B10") (pin "1") (pinfunction "NC_1") (pintype "passive"))
    )
    (net (code "158") (name "unconnected-(B11-D+-Pad3)") (class "Default")
      (node (ref "B11") (pin "3") (pinfunction "D+_3") (pintype "passive"))
    )
    (net (code "159") (name "unconnected-(B11-D--Pad4)") (class "Default")
      (node (ref "B11") (pin "4") (pinfunction "D-_4") (pintype "passive"))
    )
    (net (code "160") (name "unconnected-(B12-D1+-Pad1)") (class "Default")
      (node (ref "B12") (pin "1") (pinfunction "D1+_1") (pintype "passive"))
    )
    (net (code "161") (name "unconnected-(B12-D1--Pad2)") (class "Default")
      (node (ref "B12") (pin "2") (pinfunction "D1-_2") (pintype "passive"))
    )
    (net (code "162") (name "unconnected-(B12-N.C._1-Pad6)") (class "Default")
      (node (ref "B12") (pin "6") (pinfunction "N.C._1_6") (pintype "passive"))
    )
    (net (code "163") (name "unconnected-(B12-N.C._2-Pad7)") (class "Default")
      (node (ref "B12") (pin "7") (pinfunction "N.C._2_7") (pintype "passive"))
    )
    (net (code "164") (name "unconnected-(B12-N.C._3-Pad9)") (class "Default")
      (node (ref "B12") (pin "9") (pinfunction "N.C._3_9") (pintype "passive"))
    )
    (net (code "165") (name "unconnected-(B12-N.C._4-Pad10)") (class "Default")
      (node (ref "B12") (pin "10") (pinfunction "N.C._4_10") (pintype "passive"))
    )
    (net (code "166") (name "unconnected-(B13-EP-Pad9)") (class "Default")
      (node (ref "B13") (pin "9") (pinfunction "EP_9") (pintype "passive"))
    )
    (net (code "167") (name "unconnected-(B13-GND-Pad7)") (class "Default")
      (node (ref "B13") (pin "7") (pinfunction "GND_7") (pintype "passive"))
    )
    (net (code "168") (name "unconnected-(D1-NC-Pad2)") (class "Default")
      (node (ref "D1") (pin "2") (pinfunction "NC_2") (pintype "passive"))
    )
    (net (code "169") (name "unconnected-(J4-PadMP1)") (class "Default")
      (node (ref "J4") (pin "MP1") (pinfunction "MP1_MP1") (pintype "passive"))
    )
    (net (code "170") (name "unconnected-(J4-PadMP2)") (class "Default")
      (node (ref "J4") (pin "MP2") (pinfunction "MP2_MP2") (pintype "passive"))
    )
    (net (code "171") (name "unconnected-(J4-PadMP3)") (class "Default")
      (node (ref "J4") (pin "MP3") (pinfunction "MP3_MP3") (pintype "passive"))
    )
    (net (code "172") (name "unconnected-(J5-ID-Pad4)") (class "Default")
      (node (ref "J5") (pin "4") (pinfunction "ID_4") (pintype "bidirectional"))
    )
    (net (code "173") (name "unconnected-(P7-Pad9)") (class "Default")
      (node (ref "P7") (pin "9") (pinfunction "9_9") (pintype "passive"))
    )
    (net (code "174") (name "unconnected-(P7-Pad10)") (class "Default")
      (node (ref "P7") (pin "10") (pinfunction "10_10") (pintype "passive"))
    )
    (net (code "175") (name "unconnected-(U1A-CAMERA_GPIO-Pad97)") (class "Default")
      (node (ref "U1") (pin "97") (pinfunction "CAMERA_GPIO_97") (pintype "bidirectional"))
    )
    (net (code "176") (name "unconnected-(U1A-ETHERNET_~{LED1}-Pad19)") (class "Default")
      (node (ref "U1") (pin "19") (pinfunction "ETHERNET_~{LED1}_19") (pintype "output"))
    )
    (net (code "177") (name "unconnected-(U1A-MOUNTING_PADS-PadSH1)") (class "Default")
      (node (ref "U1") (pin "SH1") (pinfunction "MOUNTING_PADS_SH1") (pintype "passive"))
    )
    (net (code "178") (name "unconnected-(U1A-MOUNTING_PADS-PadSH2)") (class "Default")
      (node (ref "U1") (pin "SH2") (pinfunction "MOUNTING_PADS_SH2") (pintype "passive"))
    )
    (net (code "179") (name "unconnected-(U1A-MOUNTING_PADS-PadSH3)") (class "Default")
      (node (ref "U1") (pin "SH3") (pinfunction "MOUNTING_PADS_SH3") (pintype "passive"))
    )
    (net (code "180") (name "unconnected-(U1A-MOUNTING_PADS-PadSH4)") (class "Default")
      (node (ref "U1") (pin "SH4") (pinfunction "MOUNTING_PADS_SH4") (pintype "passive"))
    )
    (net (code "181") (name "unconnected-(U1A-RESERVED-Pad76)") (class "Default")
      (node (ref "U1") (pin "76") (pinfunction "RESERVED_76") (pintype "passive"))
    )
    (net (code "182") (name "unconnected-(U1A-RESERVED-Pad104)") (class "Default")
      (node (ref "U1") (pin "104") (pinfunction "RESERVED_104") (pintype "passive"))
    )
    (net (code "183") (name "unconnected-(U1A-RESERVED-Pad106)") (class "Default")
      (node (ref "U1") (pin "106") (pinfunction "RESERVED_106") (pintype "passive"))
    )
    (net (code "184") (name "unconnected-(U1A-SD_DAT4-Pad68)") (class "Default")
      (node (ref "U1") (pin "68") (pinfunction "SD_DAT4_68") (pintype "bidirectional"))
    )
    (net (code "185") (name "unconnected-(U1A-SD_DAT5-Pad64)") (class "Default")
      (node (ref "U1") (pin "64") (pinfunction "SD_DAT5_64") (pintype "bidirectional"))
    )
    (net (code "186") (name "unconnected-(U1A-SD_DAT6-Pad72)") (class "Default")
      (node (ref "U1") (pin "72") (pinfunction "SD_DAT6_72") (pintype "bidirectional"))
    )
    (net (code "187") (name "unconnected-(U1A-SD_DAT7-Pad70)") (class "Default")
      (node (ref "U1") (pin "70") (pinfunction "SD_DAT7_70") (pintype "bidirectional"))
    )
    (net (code "188") (name "unconnected-(U1A-SD_VDD_OVERRIDE-Pad73)") (class "Default")
      (node (ref "U1") (pin "73") (pinfunction "SD_VDD_OVERRIDE_73") (pintype "input"))
    )
  )
)
